# cblockyeesh.net
KiCad netlist of a schematic drawn in EAGLE
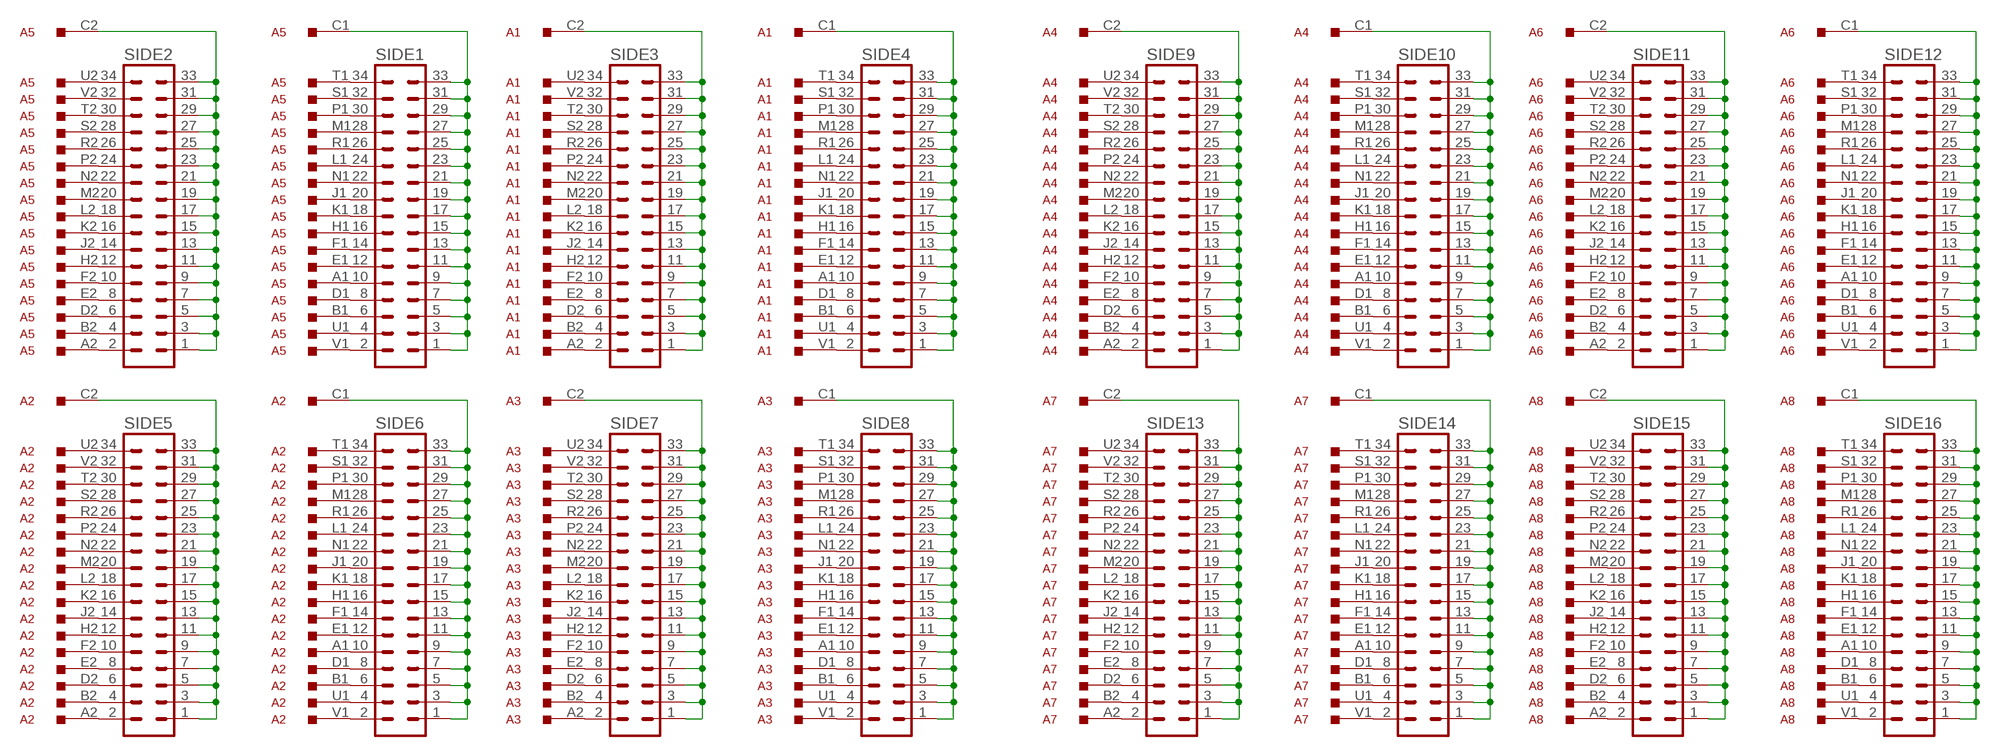
[diagram p0: schematic, sheet 1]

(export (version "E")
  (design (tool "Eeschema 10.0.6"))
  (components
    (comp (ref "A1")
      (value "M916")
      (footprint "eagle-import:H807")
      (libsource (lib "eagle-import") (part "M916"))
    )
    (comp (ref "A2")
      (value "M916")
      (footprint "eagle-import:H807")
      (libsource (lib "eagle-import") (part "M916"))
    )
    (comp (ref "A3")
      (value "M916")
      (footprint "eagle-import:H807")
      (libsource (lib "eagle-import") (part "M916"))
    )
    (comp (ref "A4")
      (value "M916")
      (footprint "eagle-import:H807")
      (libsource (lib "eagle-import") (part "M916"))
    )
    (comp (ref "A5")
      (value "M916")
      (footprint "eagle-import:H807")
      (libsource (lib "eagle-import") (part "M916"))
    )
    (comp (ref "A6")
      (value "M916")
      (footprint "eagle-import:H807")
      (libsource (lib "eagle-import") (part "M916"))
    )
    (comp (ref "A7")
      (value "M916")
      (footprint "eagle-import:H807")
      (libsource (lib "eagle-import") (part "M916"))
    )
    (comp (ref "A8")
      (value "M916")
      (footprint "eagle-import:H807")
      (libsource (lib "eagle-import") (part "M916"))
    )
    (comp (ref "SIDE1")
      (value "MA17-2")
      (footprint "eagle-import:MA17-2")
      (libsource (lib "eagle-import") (part "MA17-2"))
    )
    (comp (ref "SIDE2")
      (value "MA17-2")
      (footprint "eagle-import:MA17-2")
      (libsource (lib "eagle-import") (part "MA17-2"))
    )
    (comp (ref "SIDE3")
      (value "MA17-2")
      (footprint "eagle-import:MA17-2")
      (libsource (lib "eagle-import") (part "MA17-2"))
    )
    (comp (ref "SIDE4")
      (value "MA17-2")
      (footprint "eagle-import:MA17-2")
      (libsource (lib "eagle-import") (part "MA17-2"))
    )
    (comp (ref "SIDE5")
      (value "MA17-2")
      (footprint "eagle-import:MA17-2")
      (libsource (lib "eagle-import") (part "MA17-2"))
    )
    (comp (ref "SIDE6")
      (value "MA17-2")
      (footprint "eagle-import:MA17-2")
      (libsource (lib "eagle-import") (part "MA17-2"))
    )
    (comp (ref "SIDE7")
      (value "MA17-2")
      (footprint "eagle-import:MA17-2")
      (libsource (lib "eagle-import") (part "MA17-2"))
    )
    (comp (ref "SIDE8")
      (value "MA17-2")
      (footprint "eagle-import:MA17-2")
      (libsource (lib "eagle-import") (part "MA17-2"))
    )
    (comp (ref "SIDE9")
      (value "MA17-2")
      (footprint "eagle-import:MA17-2")
      (libsource (lib "eagle-import") (part "MA17-2"))
    )
    (comp (ref "SIDE10")
      (value "MA17-2")
      (footprint "eagle-import:MA17-2")
      (libsource (lib "eagle-import") (part "MA17-2"))
    )
    (comp (ref "SIDE11")
      (value "MA17-2")
      (footprint "eagle-import:MA17-2")
      (libsource (lib "eagle-import") (part "MA17-2"))
    )
    (comp (ref "SIDE12")
      (value "MA17-2")
      (footprint "eagle-import:MA17-2")
      (libsource (lib "eagle-import") (part "MA17-2"))
    )
    (comp (ref "SIDE13")
      (value "MA17-2")
      (footprint "eagle-import:MA17-2")
      (libsource (lib "eagle-import") (part "MA17-2"))
    )
    (comp (ref "SIDE14")
      (value "MA17-2")
      (footprint "eagle-import:MA17-2")
      (libsource (lib "eagle-import") (part "MA17-2"))
    )
    (comp (ref "SIDE15")
      (value "MA17-2")
      (footprint "eagle-import:MA17-2")
      (libsource (lib "eagle-import") (part "MA17-2"))
    )
    (comp (ref "SIDE16")
      (value "MA17-2")
      (footprint "eagle-import:MA17-2")
      (libsource (lib "eagle-import") (part "MA17-2"))
    )
  )
  (nets
    (net (code "1") (name "Net-(A1A-P$2)") (class "Default")
      (node (ref "A1") (pin "A1") (pinfunction "P$2_A1") (pintype "bidirectional"))
      (node (ref "SIDE4") (pin "10") (pinfunction "10_10") (pintype "passive"))
    )
    (net (code "2") (name "Net-(A1AA-P$2)") (class "Default")
      (node (ref "A1") (pin "R1") (pinfunction "P$2_R1") (pintype "bidirectional"))
      (node (ref "SIDE4") (pin "26") (pinfunction "26_26") (pintype "passive"))
    )
    (net (code "3") (name "Net-(A1AB-P$2)") (class "Default")
      (node (ref "A1") (pin "R2") (pinfunction "P$2_R2") (pintype "bidirectional"))
      (node (ref "SIDE3") (pin "26") (pinfunction "26_26") (pintype "passive"))
    )
    (net (code "4") (name "Net-(A1AC-P$2)") (class "Default")
      (node (ref "A1") (pin "S1") (pinfunction "P$2_S1") (pintype "bidirectional"))
      (node (ref "SIDE4") (pin "32") (pinfunction "32_32") (pintype "passive"))
    )
    (net (code "5") (name "Net-(A1AD-P$2)") (class "Default")
      (node (ref "A1") (pin "S2") (pinfunction "P$2_S2") (pintype "bidirectional"))
      (node (ref "SIDE3") (pin "28") (pinfunction "28_28") (pintype "passive"))
    )
    (net (code "6") (name "Net-(A1AE-P$2)") (class "Default")
      (node (ref "A1") (pin "T1") (pinfunction "P$2_T1") (pintype "bidirectional"))
      (node (ref "SIDE4") (pin "34") (pinfunction "34_34") (pintype "passive"))
    )
    (net (code "7") (name "Net-(A1AF-P$2)") (class "Default")
      (node (ref "A1") (pin "T2") (pinfunction "P$2_T2") (pintype "bidirectional"))
      (node (ref "SIDE3") (pin "30") (pinfunction "30_30") (pintype "passive"))
    )
    (net (code "8") (name "Net-(A1AG-P$2)") (class "Default")
      (node (ref "A1") (pin "U1") (pinfunction "P$2_U1") (pintype "bidirectional"))
      (node (ref "SIDE4") (pin "4") (pinfunction "4_4") (pintype "passive"))
    )
    (net (code "9") (name "Net-(A1AH-P$2)") (class "Default")
      (node (ref "A1") (pin "U2") (pinfunction "P$2_U2") (pintype "bidirectional"))
      (node (ref "SIDE3") (pin "34") (pinfunction "34_34") (pintype "passive"))
    )
    (net (code "10") (name "Net-(A1AI-P$2)") (class "Default")
      (node (ref "A1") (pin "V1") (pinfunction "P$2_V1") (pintype "bidirectional"))
      (node (ref "SIDE4") (pin "2") (pinfunction "2_2") (pintype "passive"))
    )
    (net (code "11") (name "Net-(A1AJ-P$2)") (class "Default")
      (node (ref "A1") (pin "V2") (pinfunction "P$2_V2") (pintype "bidirectional"))
      (node (ref "SIDE3") (pin "32") (pinfunction "32_32") (pintype "passive"))
    )
    (net (code "12") (name "Net-(A1B-P$2)") (class "Default")
      (node (ref "A1") (pin "A2") (pinfunction "P$2_A2") (pintype "bidirectional"))
      (node (ref "SIDE3") (pin "2") (pinfunction "2_2") (pintype "passive"))
    )
    (net (code "13") (name "Net-(A1C-P$2)") (class "Default")
      (node (ref "A1") (pin "B1") (pinfunction "P$2_B1") (pintype "bidirectional"))
      (node (ref "SIDE4") (pin "6") (pinfunction "6_6") (pintype "passive"))
    )
    (net (code "14") (name "Net-(A1D-P$2)") (class "Default")
      (node (ref "A1") (pin "B2") (pinfunction "P$2_B2") (pintype "bidirectional"))
      (node (ref "SIDE3") (pin "4") (pinfunction "4_4") (pintype "passive"))
    )
    (net (code "15") (name "Net-(A1E-P$2)") (class "Default")
      (node (ref "A1") (pin "C1") (pinfunction "P$2_C1") (pintype "bidirectional"))
      (node (ref "SIDE4") (pin "1") (pinfunction "1_1") (pintype "passive"))
      (node (ref "SIDE4") (pin "11") (pinfunction "11_11") (pintype "passive"))
      (node (ref "SIDE4") (pin "13") (pinfunction "13_13") (pintype "passive"))
      (node (ref "SIDE4") (pin "15") (pinfunction "15_15") (pintype "passive"))
      (node (ref "SIDE4") (pin "17") (pinfunction "17_17") (pintype "passive"))
      (node (ref "SIDE4") (pin "19") (pinfunction "19_19") (pintype "passive"))
      (node (ref "SIDE4") (pin "21") (pinfunction "21_21") (pintype "passive"))
      (node (ref "SIDE4") (pin "23") (pinfunction "23_23") (pintype "passive"))
      (node (ref "SIDE4") (pin "25") (pinfunction "25_25") (pintype "passive"))
      (node (ref "SIDE4") (pin "27") (pinfunction "27_27") (pintype "passive"))
      (node (ref "SIDE4") (pin "29") (pinfunction "29_29") (pintype "passive"))
      (node (ref "SIDE4") (pin "3") (pinfunction "3_3") (pintype "passive"))
      (node (ref "SIDE4") (pin "31") (pinfunction "31_31") (pintype "passive"))
      (node (ref "SIDE4") (pin "33") (pinfunction "33_33") (pintype "passive"))
      (node (ref "SIDE4") (pin "5") (pinfunction "5_5") (pintype "passive"))
      (node (ref "SIDE4") (pin "7") (pinfunction "7_7") (pintype "passive"))
      (node (ref "SIDE4") (pin "9") (pinfunction "9_9") (pintype "passive"))
    )
    (net (code "16") (name "Net-(A1F-P$2)") (class "Default")
      (node (ref "A1") (pin "C2") (pinfunction "P$2_C2") (pintype "bidirectional"))
      (node (ref "SIDE3") (pin "1") (pinfunction "1_1") (pintype "passive"))
      (node (ref "SIDE3") (pin "11") (pinfunction "11_11") (pintype "passive"))
      (node (ref "SIDE3") (pin "13") (pinfunction "13_13") (pintype "passive"))
      (node (ref "SIDE3") (pin "15") (pinfunction "15_15") (pintype "passive"))
      (node (ref "SIDE3") (pin "17") (pinfunction "17_17") (pintype "passive"))
      (node (ref "SIDE3") (pin "19") (pinfunction "19_19") (pintype "passive"))
      (node (ref "SIDE3") (pin "21") (pinfunction "21_21") (pintype "passive"))
      (node (ref "SIDE3") (pin "23") (pinfunction "23_23") (pintype "passive"))
      (node (ref "SIDE3") (pin "25") (pinfunction "25_25") (pintype "passive"))
      (node (ref "SIDE3") (pin "27") (pinfunction "27_27") (pintype "passive"))
      (node (ref "SIDE3") (pin "29") (pinfunction "29_29") (pintype "passive"))
      (node (ref "SIDE3") (pin "3") (pinfunction "3_3") (pintype "passive"))
      (node (ref "SIDE3") (pin "31") (pinfunction "31_31") (pintype "passive"))
      (node (ref "SIDE3") (pin "33") (pinfunction "33_33") (pintype "passive"))
      (node (ref "SIDE3") (pin "5") (pinfunction "5_5") (pintype "passive"))
      (node (ref "SIDE3") (pin "7") (pinfunction "7_7") (pintype "passive"))
      (node (ref "SIDE3") (pin "9") (pinfunction "9_9") (pintype "passive"))
    )
    (net (code "17") (name "Net-(A1G-P$2)") (class "Default")
      (node (ref "A1") (pin "D1") (pinfunction "P$2_D1") (pintype "bidirectional"))
      (node (ref "SIDE4") (pin "8") (pinfunction "8_8") (pintype "passive"))
    )
    (net (code "18") (name "Net-(A1H-P$2)") (class "Default")
      (node (ref "A1") (pin "D2") (pinfunction "P$2_D2") (pintype "bidirectional"))
      (node (ref "SIDE3") (pin "6") (pinfunction "6_6") (pintype "passive"))
    )
    (net (code "19") (name "Net-(A1I-P$2)") (class "Default")
      (node (ref "A1") (pin "E1") (pinfunction "P$2_E1") (pintype "bidirectional"))
      (node (ref "SIDE4") (pin "12") (pinfunction "12_12") (pintype "passive"))
    )
    (net (code "20") (name "Net-(A1J-P$2)") (class "Default")
      (node (ref "A1") (pin "E2") (pinfunction "P$2_E2") (pintype "bidirectional"))
      (node (ref "SIDE3") (pin "8") (pinfunction "8_8") (pintype "passive"))
    )
    (net (code "21") (name "Net-(A1K-P$2)") (class "Default")
      (node (ref "A1") (pin "F1") (pinfunction "P$2_F1") (pintype "bidirectional"))
      (node (ref "SIDE4") (pin "14") (pinfunction "14_14") (pintype "passive"))
    )
    (net (code "22") (name "Net-(A1L-P$2)") (class "Default")
      (node (ref "A1") (pin "F2") (pinfunction "P$2_F2") (pintype "bidirectional"))
      (node (ref "SIDE3") (pin "10") (pinfunction "10_10") (pintype "passive"))
    )
    (net (code "23") (name "Net-(A1M-P$2)") (class "Default")
      (node (ref "A1") (pin "H1") (pinfunction "P$2_H1") (pintype "bidirectional"))
      (node (ref "SIDE4") (pin "16") (pinfunction "16_16") (pintype "passive"))
    )
    (net (code "24") (name "Net-(A1N-P$2)") (class "Default")
      (node (ref "A1") (pin "H2") (pinfunction "P$2_H2") (pintype "bidirectional"))
      (node (ref "SIDE3") (pin "12") (pinfunction "12_12") (pintype "passive"))
    )
    (net (code "25") (name "Net-(A1O-P$2)") (class "Default")
      (node (ref "A1") (pin "J1") (pinfunction "P$2_J1") (pintype "bidirectional"))
      (node (ref "SIDE4") (pin "20") (pinfunction "20_20") (pintype "passive"))
    )
    (net (code "26") (name "Net-(A1P-P$2)") (class "Default")
      (node (ref "A1") (pin "J2") (pinfunction "P$2_J2") (pintype "bidirectional"))
      (node (ref "SIDE3") (pin "14") (pinfunction "14_14") (pintype "passive"))
    )
    (net (code "27") (name "Net-(A1Q-P$2)") (class "Default")
      (node (ref "A1") (pin "K1") (pinfunction "P$2_K1") (pintype "bidirectional"))
      (node (ref "SIDE4") (pin "18") (pinfunction "18_18") (pintype "passive"))
    )
    (net (code "28") (name "Net-(A1R-P$2)") (class "Default")
      (node (ref "A1") (pin "K2") (pinfunction "P$2_K2") (pintype "bidirectional"))
      (node (ref "SIDE3") (pin "16") (pinfunction "16_16") (pintype "passive"))
    )
    (net (code "29") (name "Net-(A1S-P$2)") (class "Default")
      (node (ref "A1") (pin "L1") (pinfunction "P$2_L1") (pintype "bidirectional"))
      (node (ref "SIDE4") (pin "24") (pinfunction "24_24") (pintype "passive"))
    )
    (net (code "30") (name "Net-(A1T-P$2)") (class "Default")
      (node (ref "A1") (pin "L2") (pinfunction "P$2_L2") (pintype "bidirectional"))
      (node (ref "SIDE3") (pin "18") (pinfunction "18_18") (pintype "passive"))
    )
    (net (code "31") (name "Net-(A1U-P$2)") (class "Default")
      (node (ref "A1") (pin "M1") (pinfunction "P$2_M1") (pintype "bidirectional"))
      (node (ref "SIDE4") (pin "28") (pinfunction "28_28") (pintype "passive"))
    )
    (net (code "32") (name "Net-(A1V-P$2)") (class "Default")
      (node (ref "A1") (pin "M2") (pinfunction "P$2_M2") (pintype "bidirectional"))
      (node (ref "SIDE3") (pin "20") (pinfunction "20_20") (pintype "passive"))
    )
    (net (code "33") (name "Net-(A1W-P$2)") (class "Default")
      (node (ref "A1") (pin "N1") (pinfunction "P$2_N1") (pintype "bidirectional"))
      (node (ref "SIDE4") (pin "22") (pinfunction "22_22") (pintype "passive"))
    )
    (net (code "34") (name "Net-(A1X-P$2)") (class "Default")
      (node (ref "A1") (pin "N2") (pinfunction "P$2_N2") (pintype "bidirectional"))
      (node (ref "SIDE3") (pin "22") (pinfunction "22_22") (pintype "passive"))
    )
    (net (code "35") (name "Net-(A1Y-P$2)") (class "Default")
      (node (ref "A1") (pin "P1") (pinfunction "P$2_P1") (pintype "bidirectional"))
      (node (ref "SIDE4") (pin "30") (pinfunction "30_30") (pintype "passive"))
    )
    (net (code "36") (name "Net-(A1Z-P$2)") (class "Default")
      (node (ref "A1") (pin "P2") (pinfunction "P$2_P2") (pintype "bidirectional"))
      (node (ref "SIDE3") (pin "24") (pinfunction "24_24") (pintype "passive"))
    )
    (net (code "37") (name "Net-(A2A-P$2)") (class "Default")
      (node (ref "A2") (pin "A1") (pinfunction "P$2_A1") (pintype "bidirectional"))
      (node (ref "SIDE6") (pin "10") (pinfunction "10_10") (pintype "passive"))
    )
    (net (code "38") (name "Net-(A2AA-P$2)") (class "Default")
      (node (ref "A2") (pin "R1") (pinfunction "P$2_R1") (pintype "bidirectional"))
      (node (ref "SIDE6") (pin "26") (pinfunction "26_26") (pintype "passive"))
    )
    (net (code "39") (name "Net-(A2AB-P$2)") (class "Default")
      (node (ref "A2") (pin "R2") (pinfunction "P$2_R2") (pintype "bidirectional"))
      (node (ref "SIDE5") (pin "26") (pinfunction "26_26") (pintype "passive"))
    )
    (net (code "40") (name "Net-(A2AC-P$2)") (class "Default")
      (node (ref "A2") (pin "S1") (pinfunction "P$2_S1") (pintype "bidirectional"))
      (node (ref "SIDE6") (pin "32") (pinfunction "32_32") (pintype "passive"))
    )
    (net (code "41") (name "Net-(A2AD-P$2)") (class "Default")
      (node (ref "A2") (pin "S2") (pinfunction "P$2_S2") (pintype "bidirectional"))
      (node (ref "SIDE5") (pin "28") (pinfunction "28_28") (pintype "passive"))
    )
    (net (code "42") (name "Net-(A2AE-P$2)") (class "Default")
      (node (ref "A2") (pin "T1") (pinfunction "P$2_T1") (pintype "bidirectional"))
      (node (ref "SIDE6") (pin "34") (pinfunction "34_34") (pintype "passive"))
    )
    (net (code "43") (name "Net-(A2AF-P$2)") (class "Default")
      (node (ref "A2") (pin "T2") (pinfunction "P$2_T2") (pintype "bidirectional"))
      (node (ref "SIDE5") (pin "30") (pinfunction "30_30") (pintype "passive"))
    )
    (net (code "44") (name "Net-(A2AG-P$2)") (class "Default")
      (node (ref "A2") (pin "U1") (pinfunction "P$2_U1") (pintype "bidirectional"))
      (node (ref "SIDE6") (pin "4") (pinfunction "4_4") (pintype "passive"))
    )
    (net (code "45") (name "Net-(A2AH-P$2)") (class "Default")
      (node (ref "A2") (pin "U2") (pinfunction "P$2_U2") (pintype "bidirectional"))
      (node (ref "SIDE5") (pin "34") (pinfunction "34_34") (pintype "passive"))
    )
    (net (code "46") (name "Net-(A2AI-P$2)") (class "Default")
      (node (ref "A2") (pin "V1") (pinfunction "P$2_V1") (pintype "bidirectional"))
      (node (ref "SIDE6") (pin "2") (pinfunction "2_2") (pintype "passive"))
    )
    (net (code "47") (name "Net-(A2AJ-P$2)") (class "Default")
      (node (ref "A2") (pin "V2") (pinfunction "P$2_V2") (pintype "bidirectional"))
      (node (ref "SIDE5") (pin "32") (pinfunction "32_32") (pintype "passive"))
    )
    (net (code "48") (name "Net-(A2B-P$2)") (class "Default")
      (node (ref "A2") (pin "A2") (pinfunction "P$2_A2") (pintype "bidirectional"))
      (node (ref "SIDE5") (pin "2") (pinfunction "2_2") (pintype "passive"))
    )
    (net (code "49") (name "Net-(A2C-P$2)") (class "Default")
      (node (ref "A2") (pin "B1") (pinfunction "P$2_B1") (pintype "bidirectional"))
      (node (ref "SIDE6") (pin "6") (pinfunction "6_6") (pintype "passive"))
    )
    (net (code "50") (name "Net-(A2D-P$2)") (class "Default")
      (node (ref "A2") (pin "B2") (pinfunction "P$2_B2") (pintype "bidirectional"))
      (node (ref "SIDE5") (pin "4") (pinfunction "4_4") (pintype "passive"))
    )
    (net (code "51") (name "Net-(A2E-P$2)") (class "Default")
      (node (ref "A2") (pin "C1") (pinfunction "P$2_C1") (pintype "bidirectional"))
      (node (ref "SIDE6") (pin "1") (pinfunction "1_1") (pintype "passive"))
      (node (ref "SIDE6") (pin "11") (pinfunction "11_11") (pintype "passive"))
      (node (ref "SIDE6") (pin "13") (pinfunction "13_13") (pintype "passive"))
      (node (ref "SIDE6") (pin "15") (pinfunction "15_15") (pintype "passive"))
      (node (ref "SIDE6") (pin "17") (pinfunction "17_17") (pintype "passive"))
      (node (ref "SIDE6") (pin "19") (pinfunction "19_19") (pintype "passive"))
      (node (ref "SIDE6") (pin "21") (pinfunction "21_21") (pintype "passive"))
      (node (ref "SIDE6") (pin "23") (pinfunction "23_23") (pintype "passive"))
      (node (ref "SIDE6") (pin "25") (pinfunction "25_25") (pintype "passive"))
      (node (ref "SIDE6") (pin "27") (pinfunction "27_27") (pintype "passive"))
      (node (ref "SIDE6") (pin "29") (pinfunction "29_29") (pintype "passive"))
      (node (ref "SIDE6") (pin "3") (pinfunction "3_3") (pintype "passive"))
      (node (ref "SIDE6") (pin "31") (pinfunction "31_31") (pintype "passive"))
      (node (ref "SIDE6") (pin "33") (pinfunction "33_33") (pintype "passive"))
      (node (ref "SIDE6") (pin "5") (pinfunction "5_5") (pintype "passive"))
      (node (ref "SIDE6") (pin "7") (pinfunction "7_7") (pintype "passive"))
      (node (ref "SIDE6") (pin "9") (pinfunction "9_9") (pintype "passive"))
    )
    (net (code "52") (name "Net-(A2F-P$2)") (class "Default")
      (node (ref "A2") (pin "C2") (pinfunction "P$2_C2") (pintype "bidirectional"))
      (node (ref "SIDE5") (pin "1") (pinfunction "1_1") (pintype "passive"))
      (node (ref "SIDE5") (pin "11") (pinfunction "11_11") (pintype "passive"))
      (node (ref "SIDE5") (pin "13") (pinfunction "13_13") (pintype "passive"))
      (node (ref "SIDE5") (pin "15") (pinfunction "15_15") (pintype "passive"))
      (node (ref "SIDE5") (pin "17") (pinfunction "17_17") (pintype "passive"))
      (node (ref "SIDE5") (pin "19") (pinfunction "19_19") (pintype "passive"))
      (node (ref "SIDE5") (pin "21") (pinfunction "21_21") (pintype "passive"))
      (node (ref "SIDE5") (pin "23") (pinfunction "23_23") (pintype "passive"))
      (node (ref "SIDE5") (pin "25") (pinfunction "25_25") (pintype "passive"))
      (node (ref "SIDE5") (pin "27") (pinfunction "27_27") (pintype "passive"))
      (node (ref "SIDE5") (pin "29") (pinfunction "29_29") (pintype "passive"))
      (node (ref "SIDE5") (pin "3") (pinfunction "3_3") (pintype "passive"))
      (node (ref "SIDE5") (pin "31") (pinfunction "31_31") (pintype "passive"))
      (node (ref "SIDE5") (pin "33") (pinfunction "33_33") (pintype "passive"))
      (node (ref "SIDE5") (pin "5") (pinfunction "5_5") (pintype "passive"))
      (node (ref "SIDE5") (pin "7") (pinfunction "7_7") (pintype "passive"))
      (node (ref "SIDE5") (pin "9") (pinfunction "9_9") (pintype "passive"))
    )
    (net (code "53") (name "Net-(A2G-P$2)") (class "Default")
      (node (ref "A2") (pin "D1") (pinfunction "P$2_D1") (pintype "bidirectional"))
      (node (ref "SIDE6") (pin "8") (pinfunction "8_8") (pintype "passive"))
    )
    (net (code "54") (name "Net-(A2H-P$2)") (class "Default")
      (node (ref "A2") (pin "D2") (pinfunction "P$2_D2") (pintype "bidirectional"))
      (node (ref "SIDE5") (pin "6") (pinfunction "6_6") (pintype "passive"))
    )
    (net (code "55") (name "Net-(A2I-P$2)") (class "Default")
      (node (ref "A2") (pin "E1") (pinfunction "P$2_E1") (pintype "bidirectional"))
      (node (ref "SIDE6") (pin "12") (pinfunction "12_12") (pintype "passive"))
    )
    (net (code "56") (name "Net-(A2J-P$2)") (class "Default")
      (node (ref "A2") (pin "E2") (pinfunction "P$2_E2") (pintype "bidirectional"))
      (node (ref "SIDE5") (pin "8") (pinfunction "8_8") (pintype "passive"))
    )
    (net (code "57") (name "Net-(A2K-P$2)") (class "Default")
      (node (ref "A2") (pin "F1") (pinfunction "P$2_F1") (pintype "bidirectional"))
      (node (ref "SIDE6") (pin "14") (pinfunction "14_14") (pintype "passive"))
    )
    (net (code "58") (name "Net-(A2L-P$2)") (class "Default")
      (node (ref "A2") (pin "F2") (pinfunction "P$2_F2") (pintype "bidirectional"))
      (node (ref "SIDE5") (pin "10") (pinfunction "10_10") (pintype "passive"))
    )
    (net (code "59") (name "Net-(A2M-P$2)") (class "Default")
      (node (ref "A2") (pin "H1") (pinfunction "P$2_H1") (pintype "bidirectional"))
      (node (ref "SIDE6") (pin "16") (pinfunction "16_16") (pintype "passive"))
    )
    (net (code "60") (name "Net-(A2N-P$2)") (class "Default")
      (node (ref "A2") (pin "H2") (pinfunction "P$2_H2") (pintype "bidirectional"))
      (node (ref "SIDE5") (pin "12") (pinfunction "12_12") (pintype "passive"))
    )
    (net (code "61") (name "Net-(A2O-P$2)") (class "Default")
      (node (ref "A2") (pin "J1") (pinfunction "P$2_J1") (pintype "bidirectional"))
      (node (ref "SIDE6") (pin "20") (pinfunction "20_20") (pintype "passive"))
    )
    (net (code "62") (name "Net-(A2P-P$2)") (class "Default")
      (node (ref "A2") (pin "J2") (pinfunction "P$2_J2") (pintype "bidirectional"))
      (node (ref "SIDE5") (pin "14") (pinfunction "14_14") (pintype "passive"))
    )
    (net (code "63") (name "Net-(A2Q-P$2)") (class "Default")
      (node (ref "A2") (pin "K1") (pinfunction "P$2_K1") (pintype "bidirectional"))
      (node (ref "SIDE6") (pin "18") (pinfunction "18_18") (pintype "passive"))
    )
    (net (code "64") (name "Net-(A2R-P$2)") (class "Default")
      (node (ref "A2") (pin "K2") (pinfunction "P$2_K2") (pintype "bidirectional"))
      (node (ref "SIDE5") (pin "16") (pinfunction "16_16") (pintype "passive"))
    )
    (net (code "65") (name "Net-(A2S-P$2)") (class "Default")
      (node (ref "A2") (pin "L1") (pinfunction "P$2_L1") (pintype "bidirectional"))
      (node (ref "SIDE6") (pin "24") (pinfunction "24_24") (pintype "passive"))
    )
    (net (code "66") (name "Net-(A2T-P$2)") (class "Default")
      (node (ref "A2") (pin "L2") (pinfunction "P$2_L2") (pintype "bidirectional"))
      (node (ref "SIDE5") (pin "18") (pinfunction "18_18") (pintype "passive"))
    )
    (net (code "67") (name "Net-(A2U-P$2)") (class "Default")
      (node (ref "A2") (pin "M1") (pinfunction "P$2_M1") (pintype "bidirectional"))
      (node (ref "SIDE6") (pin "28") (pinfunction "28_28") (pintype "passive"))
    )
    (net (code "68") (name "Net-(A2V-P$2)") (class "Default")
      (node (ref "A2") (pin "M2") (pinfunction "P$2_M2") (pintype "bidirectional"))
      (node (ref "SIDE5") (pin "20") (pinfunction "20_20") (pintype "passive"))
    )
    (net (code "69") (name "Net-(A2W-P$2)") (class "Default")
      (node (ref "A2") (pin "N1") (pinfunction "P$2_N1") (pintype "bidirectional"))
      (node (ref "SIDE6") (pin "22") (pinfunction "22_22") (pintype "passive"))
    )
    (net (code "70") (name "Net-(A2X-P$2)") (class "Default")
      (node (ref "A2") (pin "N2") (pinfunction "P$2_N2") (pintype "bidirectional"))
      (node (ref "SIDE5") (pin "22") (pinfunction "22_22") (pintype "passive"))
    )
    (net (code "71") (name "Net-(A2Y-P$2)") (class "Default")
      (node (ref "A2") (pin "P1") (pinfunction "P$2_P1") (pintype "bidirectional"))
      (node (ref "SIDE6") (pin "30") (pinfunction "30_30") (pintype "passive"))
    )
    (net (code "72") (name "Net-(A2Z-P$2)") (class "Default")
      (node (ref "A2") (pin "P2") (pinfunction "P$2_P2") (pintype "bidirectional"))
      (node (ref "SIDE5") (pin "24") (pinfunction "24_24") (pintype "passive"))
    )
    (net (code "73") (name "Net-(A3A-P$2)") (class "Default")
      (node (ref "A3") (pin "A1") (pinfunction "P$2_A1") (pintype "bidirectional"))
      (node (ref "SIDE8") (pin "10") (pinfunction "10_10") (pintype "passive"))
    )
    (net (code "74") (name "Net-(A3AA-P$2)") (class "Default")
      (node (ref "A3") (pin "R1") (pinfunction "P$2_R1") (pintype "bidirectional"))
      (node (ref "SIDE8") (pin "26") (pinfunction "26_26") (pintype "passive"))
    )
    (net (code "75") (name "Net-(A3AB-P$2)") (class "Default")
      (node (ref "A3") (pin "R2") (pinfunction "P$2_R2") (pintype "bidirectional"))
      (node (ref "SIDE7") (pin "26") (pinfunction "26_26") (pintype "passive"))
    )
    (net (code "76") (name "Net-(A3AC-P$2)") (class "Default")
      (node (ref "A3") (pin "S1") (pinfunction "P$2_S1") (pintype "bidirectional"))
      (node (ref "SIDE8") (pin "32") (pinfunction "32_32") (pintype "passive"))
    )
    (net (code "77") (name "Net-(A3AD-P$2)") (class "Default")
      (node (ref "A3") (pin "S2") (pinfunction "P$2_S2") (pintype "bidirectional"))
      (node (ref "SIDE7") (pin "28") (pinfunction "28_28") (pintype "passive"))
    )
    (net (code "78") (name "Net-(A3AE-P$2)") (class "Default")
      (node (ref "A3") (pin "T1") (pinfunction "P$2_T1") (pintype "bidirectional"))
      (node (ref "SIDE8") (pin "34") (pinfunction "34_34") (pintype "passive"))
    )
    (net (code "79") (name "Net-(A3AF-P$2)") (class "Default")
      (node (ref "A3") (pin "T2") (pinfunction "P$2_T2") (pintype "bidirectional"))
      (node (ref "SIDE7") (pin "30") (pinfunction "30_30") (pintype "passive"))
    )
    (net (code "80") (name "Net-(A3AG-P$2)") (class "Default")
      (node (ref "A3") (pin "U1") (pinfunction "P$2_U1") (pintype "bidirectional"))
      (node (ref "SIDE8") (pin "4") (pinfunction "4_4") (pintype "passive"))
    )
    (net (code "81") (name "Net-(A3AH-P$2)") (class "Default")
      (node (ref "A3") (pin "U2") (pinfunction "P$2_U2") (pintype "bidirectional"))
      (node (ref "SIDE7") (pin "34") (pinfunction "34_34") (pintype "passive"))
    )
    (net (code "82") (name "Net-(A3AI-P$2)") (class "Default")
      (node (ref "A3") (pin "V1") (pinfunction "P$2_V1") (pintype "bidirectional"))
      (node (ref "SIDE8") (pin "2") (pinfunction "2_2") (pintype "passive"))
    )
    (net (code "83") (name "Net-(A3AJ-P$2)") (class "Default")
      (node (ref "A3") (pin "V2") (pinfunction "P$2_V2") (pintype "bidirectional"))
      (node (ref "SIDE7") (pin "32") (pinfunction "32_32") (pintype "passive"))
    )
    (net (code "84") (name "Net-(A3B-P$2)") (class "Default")
      (node (ref "A3") (pin "A2") (pinfunction "P$2_A2") (pintype "bidirectional"))
      (node (ref "SIDE7") (pin "2") (pinfunction "2_2") (pintype "passive"))
    )
    (net (code "85") (name "Net-(A3C-P$2)") (class "Default")
      (node (ref "A3") (pin "B1") (pinfunction "P$2_B1") (pintype "bidirectional"))
      (node (ref "SIDE8") (pin "6") (pinfunction "6_6") (pintype "passive"))
    )
    (net (code "86") (name "Net-(A3D-P$2)") (class "Default")
      (node (ref "A3") (pin "B2") (pinfunction "P$2_B2") (pintype "bidirectional"))
      (node (ref "SIDE7") (pin "4") (pinfunction "4_4") (pintype "passive"))
    )
    (net (code "87") (name "Net-(A3E-P$2)") (class "Default")
      (node (ref "A3") (pin "C1") (pinfunction "P$2_C1") (pintype "bidirectional"))
      (node (ref "SIDE8") (pin "1") (pinfunction "1_1") (pintype "passive"))
      (node (ref "SIDE8") (pin "11") (pinfunction "11_11") (pintype "passive"))
      (node (ref "SIDE8") (pin "13") (pinfunction "13_13") (pintype "passive"))
      (node (ref "SIDE8") (pin "15") (pinfunction "15_15") (pintype "passive"))
      (node (ref "SIDE8") (pin "17") (pinfunction "17_17") (pintype "passive"))
      (node (ref "SIDE8") (pin "19") (pinfunction "19_19") (pintype "passive"))
      (node (ref "SIDE8") (pin "21") (pinfunction "21_21") (pintype "passive"))
      (node (ref "SIDE8") (pin "23") (pinfunction "23_23") (pintype "passive"))
      (node (ref "SIDE8") (pin "25") (pinfunction "25_25") (pintype "passive"))
      (node (ref "SIDE8") (pin "27") (pinfunction "27_27") (pintype "passive"))
      (node (ref "SIDE8") (pin "29") (pinfunction "29_29") (pintype "passive"))
      (node (ref "SIDE8") (pin "3") (pinfunction "3_3") (pintype "passive"))
      (node (ref "SIDE8") (pin "31") (pinfunction "31_31") (pintype "passive"))
      (node (ref "SIDE8") (pin "33") (pinfunction "33_33") (pintype "passive"))
      (node (ref "SIDE8") (pin "5") (pinfunction "5_5") (pintype "passive"))
      (node (ref "SIDE8") (pin "7") (pinfunction "7_7") (pintype "passive"))
      (node (ref "SIDE8") (pin "9") (pinfunction "9_9") (pintype "passive"))
    )
    (net (code "88") (name "Net-(A3F-P$2)") (class "Default")
      (node (ref "A3") (pin "C2") (pinfunction "P$2_C2") (pintype "bidirectional"))
      (node (ref "SIDE7") (pin "1") (pinfunction "1_1") (pintype "passive"))
      (node (ref "SIDE7") (pin "11") (pinfunction "11_11") (pintype "passive"))
      (node (ref "SIDE7") (pin "13") (pinfunction "13_13") (pintype "passive"))
      (node (ref "SIDE7") (pin "15") (pinfunction "15_15") (pintype "passive"))
      (node (ref "SIDE7") (pin "17") (pinfunction "17_17") (pintype "passive"))
      (node (ref "SIDE7") (pin "19") (pinfunction "19_19") (pintype "passive"))
      (node (ref "SIDE7") (pin "21") (pinfunction "21_21") (pintype "passive"))
      (node (ref "SIDE7") (pin "23") (pinfunction "23_23") (pintype "passive"))
      (node (ref "SIDE7") (pin "25") (pinfunction "25_25") (pintype "passive"))
      (node (ref "SIDE7") (pin "27") (pinfunction "27_27") (pintype "passive"))
      (node (ref "SIDE7") (pin "29") (pinfunction "29_29") (pintype "passive"))
      (node (ref "SIDE7") (pin "3") (pinfunction "3_3") (pintype "passive"))
      (node (ref "SIDE7") (pin "31") (pinfunction "31_31") (pintype "passive"))
      (node (ref "SIDE7") (pin "33") (pinfunction "33_33") (pintype "passive"))
      (node (ref "SIDE7") (pin "5") (pinfunction "5_5") (pintype "passive"))
      (node (ref "SIDE7") (pin "7") (pinfunction "7_7") (pintype "passive"))
      (node (ref "SIDE7") (pin "9") (pinfunction "9_9") (pintype "passive"))
    )
    (net (code "89") (name "Net-(A3G-P$2)") (class "Default")
      (node (ref "A3") (pin "D1") (pinfunction "P$2_D1") (pintype "bidirectional"))
      (node (ref "SIDE8") (pin "8") (pinfunction "8_8") (pintype "passive"))
    )
    (net (code "90") (name "Net-(A3H-P$2)") (class "Default")
      (node (ref "A3") (pin "D2") (pinfunction "P$2_D2") (pintype "bidirectional"))
      (node (ref "SIDE7") (pin "6") (pinfunction "6_6") (pintype "passive"))
    )
    (net (code "91") (name "Net-(A3I-P$2)") (class "Default")
      (node (ref "A3") (pin "E1") (pinfunction "P$2_E1") (pintype "bidirectional"))
      (node (ref "SIDE8") (pin "12") (pinfunction "12_12") (pintype "passive"))
    )
    (net (code "92") (name "Net-(A3J-P$2)") (class "Default")
      (node (ref "A3") (pin "E2") (pinfunction "P$2_E2") (pintype "bidirectional"))
      (node (ref "SIDE7") (pin "8") (pinfunction "8_8") (pintype "passive"))
    )
    (net (code "93") (name "Net-(A3K-P$2)") (class "Default")
      (node (ref "A3") (pin "F1") (pinfunction "P$2_F1") (pintype "bidirectional"))
      (node (ref "SIDE8") (pin "14") (pinfunction "14_14") (pintype "passive"))
    )
    (net (code "94") (name "Net-(A3L-P$2)") (class "Default")
      (node (ref "A3") (pin "F2") (pinfunction "P$2_F2") (pintype "bidirectional"))
      (node (ref "SIDE7") (pin "10") (pinfunction "10_10") (pintype "passive"))
    )
    (net (code "95") (name "Net-(A3M-P$2)") (class "Default")
      (node (ref "A3") (pin "H1") (pinfunction "P$2_H1") (pintype "bidirectional"))
      (node (ref "SIDE8") (pin "16") (pinfunction "16_16") (pintype "passive"))
    )
    (net (code "96") (name "Net-(A3N-P$2)") (class "Default")
      (node (ref "A3") (pin "H2") (pinfunction "P$2_H2") (pintype "bidirectional"))
      (node (ref "SIDE7") (pin "12") (pinfunction "12_12") (pintype "passive"))
    )
    (net (code "97") (name "Net-(A3O-P$2)") (class "Default")
      (node (ref "A3") (pin "J1") (pinfunction "P$2_J1") (pintype "bidirectional"))
      (node (ref "SIDE8") (pin "20") (pinfunction "20_20") (pintype "passive"))
    )
    (net (code "98") (name "Net-(A3P-P$2)") (class "Default")
      (node (ref "A3") (pin "J2") (pinfunction "P$2_J2") (pintype "bidirectional"))
      (node (ref "SIDE7") (pin "14") (pinfunction "14_14") (pintype "passive"))
    )
    (net (code "99") (name "Net-(A3Q-P$2)") (class "Default")
      (node (ref "A3") (pin "K1") (pinfunction "P$2_K1") (pintype "bidirectional"))
      (node (ref "SIDE8") (pin "18") (pinfunction "18_18") (pintype "passive"))
    )
    (net (code "100") (name "Net-(A3R-P$2)") (class "Default")
      (node (ref "A3") (pin "K2") (pinfunction "P$2_K2") (pintype "bidirectional"))
      (node (ref "SIDE7") (pin "16") (pinfunction "16_16") (pintype "passive"))
    )
    (net (code "101") (name "Net-(A3S-P$2)") (class "Default")
      (node (ref "A3") (pin "L1") (pinfunction "P$2_L1") (pintype "bidirectional"))
      (node (ref "SIDE8") (pin "24") (pinfunction "24_24") (pintype "passive"))
    )
    (net (code "102") (name "Net-(A3T-P$2)") (class "Default")
      (node (ref "A3") (pin "L2") (pinfunction "P$2_L2") (pintype "bidirectional"))
      (node (ref "SIDE7") (pin "18") (pinfunction "18_18") (pintype "passive"))
    )
    (net (code "103") (name "Net-(A3U-P$2)") (class "Default")
      (node (ref "A3") (pin "M1") (pinfunction "P$2_M1") (pintype "bidirectional"))
      (node (ref "SIDE8") (pin "28") (pinfunction "28_28") (pintype "passive"))
    )
    (net (code "104") (name "Net-(A3V-P$2)") (class "Default")
      (node (ref "A3") (pin "M2") (pinfunction "P$2_M2") (pintype "bidirectional"))
      (node (ref "SIDE7") (pin "20") (pinfunction "20_20") (pintype "passive"))
    )
    (net (code "105") (name "Net-(A3W-P$2)") (class "Default")
      (node (ref "A3") (pin "N1") (pinfunction "P$2_N1") (pintype "bidirectional"))
      (node (ref "SIDE8") (pin "22") (pinfunction "22_22") (pintype "passive"))
    )
    (net (code "106") (name "Net-(A3X-P$2)") (class "Default")
      (node (ref "A3") (pin "N2") (pinfunction "P$2_N2") (pintype "bidirectional"))
      (node (ref "SIDE7") (pin "22") (pinfunction "22_22") (pintype "passive"))
    )
    (net (code "107") (name "Net-(A3Y-P$2)") (class "Default")
      (node (ref "A3") (pin "P1") (pinfunction "P$2_P1") (pintype "bidirectional"))
      (node (ref "SIDE8") (pin "30") (pinfunction "30_30") (pintype "passive"))
    )
    (net (code "108") (name "Net-(A3Z-P$2)") (class "Default")
      (node (ref "A3") (pin "P2") (pinfunction "P$2_P2") (pintype "bidirectional"))
      (node (ref "SIDE7") (pin "24") (pinfunction "24_24") (pintype "passive"))
    )
    (net (code "109") (name "Net-(A4A-P$2)") (class "Default")
      (node (ref "A4") (pin "A1") (pinfunction "P$2_A1") (pintype "bidirectional"))
      (node (ref "SIDE10") (pin "10") (pinfunction "10_10") (pintype "passive"))
    )
    (net (code "110") (name "Net-(A4AA-P$2)") (class "Default")
      (node (ref "A4") (pin "R1") (pinfunction "P$2_R1") (pintype "bidirectional"))
      (node (ref "SIDE10") (pin "26") (pinfunction "26_26") (pintype "passive"))
    )
    (net (code "111") (name "Net-(A4AB-P$2)") (class "Default")
      (node (ref "A4") (pin "R2") (pinfunction "P$2_R2") (pintype "bidirectional"))
      (node (ref "SIDE9") (pin "26") (pinfunction "26_26") (pintype "passive"))
    )
    (net (code "112") (name "Net-(A4AC-P$2)") (class "Default")
      (node (ref "A4") (pin "S1") (pinfunction "P$2_S1") (pintype "bidirectional"))
      (node (ref "SIDE10") (pin "32") (pinfunction "32_32") (pintype "passive"))
    )
    (net (code "113") (name "Net-(A4AD-P$2)") (class "Default")
      (node (ref "A4") (pin "S2") (pinfunction "P$2_S2") (pintype "bidirectional"))
      (node (ref "SIDE9") (pin "28") (pinfunction "28_28") (pintype "passive"))
    )
    (net (code "114") (name "Net-(A4AE-P$2)") (class "Default")
      (node (ref "A4") (pin "T1") (pinfunction "P$2_T1") (pintype "bidirectional"))
      (node (ref "SIDE10") (pin "34") (pinfunction "34_34") (pintype "passive"))
    )
    (net (code "115") (name "Net-(A4AF-P$2)") (class "Default")
      (node (ref "A4") (pin "T2") (pinfunction "P$2_T2") (pintype "bidirectional"))
      (node (ref "SIDE9") (pin "30") (pinfunction "30_30") (pintype "passive"))
    )
    (net (code "116") (name "Net-(A4AG-P$2)") (class "Default")
      (node (ref "A4") (pin "U1") (pinfunction "P$2_U1") (pintype "bidirectional"))
      (node (ref "SIDE10") (pin "4") (pinfunction "4_4") (pintype "passive"))
    )
    (net (code "117") (name "Net-(A4AH-P$2)") (class "Default")
      (node (ref "A4") (pin "U2") (pinfunction "P$2_U2") (pintype "bidirectional"))
      (node (ref "SIDE9") (pin "34") (pinfunction "34_34") (pintype "passive"))
    )
    (net (code "118") (name "Net-(A4AI-P$2)") (class "Default")
      (node (ref "A4") (pin "V1") (pinfunction "P$2_V1") (pintype "bidirectional"))
      (node (ref "SIDE10") (pin "2") (pinfunction "2_2") (pintype "passive"))
    )
    (net (code "119") (name "Net-(A4AJ-P$2)") (class "Default")
      (node (ref "A4") (pin "V2") (pinfunction "P$2_V2") (pintype "bidirectional"))
      (node (ref "SIDE9") (pin "32") (pinfunction "32_32") (pintype "passive"))
    )
    (net (code "120") (name "Net-(A4B-P$2)") (class "Default")
      (node (ref "A4") (pin "A2") (pinfunction "P$2_A2") (pintype "bidirectional"))
      (node (ref "SIDE9") (pin "2") (pinfunction "2_2") (pintype "passive"))
    )
    (net (code "121") (name "Net-(A4C-P$2)") (class "Default")
      (node (ref "A4") (pin "B1") (pinfunction "P$2_B1") (pintype "bidirectional"))
      (node (ref "SIDE10") (pin "6") (pinfunction "6_6") (pintype "passive"))
    )
    (net (code "122") (name "Net-(A4D-P$2)") (class "Default")
      (node (ref "A4") (pin "B2") (pinfunction "P$2_B2") (pintype "bidirectional"))
      (node (ref "SIDE9") (pin "4") (pinfunction "4_4") (pintype "passive"))
    )
    (net (code "123") (name "Net-(A4E-P$2)") (class "Default")
      (node (ref "A4") (pin "C1") (pinfunction "P$2_C1") (pintype "bidirectional"))
      (node (ref "SIDE10") (pin "1") (pinfunction "1_1") (pintype "passive"))
      (node (ref "SIDE10") (pin "11") (pinfunction "11_11") (pintype "passive"))
      (node (ref "SIDE10") (pin "13") (pinfunction "13_13") (pintype "passive"))
      (node (ref "SIDE10") (pin "15") (pinfunction "15_15") (pintype "passive"))
      (node (ref "SIDE10") (pin "17") (pinfunction "17_17") (pintype "passive"))
      (node (ref "SIDE10") (pin "19") (pinfunction "19_19") (pintype "passive"))
      (node (ref "SIDE10") (pin "21") (pinfunction "21_21") (pintype "passive"))
      (node (ref "SIDE10") (pin "23") (pinfunction "23_23") (pintype "passive"))
      (node (ref "SIDE10") (pin "25") (pinfunction "25_25") (pintype "passive"))
      (node (ref "SIDE10") (pin "27") (pinfunction "27_27") (pintype "passive"))
      (node (ref "SIDE10") (pin "29") (pinfunction "29_29") (pintype "passive"))
      (node (ref "SIDE10") (pin "3") (pinfunction "3_3") (pintype "passive"))
      (node (ref "SIDE10") (pin "31") (pinfunction "31_31") (pintype "passive"))
      (node (ref "SIDE10") (pin "33") (pinfunction "33_33") (pintype "passive"))
      (node (ref "SIDE10") (pin "5") (pinfunction "5_5") (pintype "passive"))
      (node (ref "SIDE10") (pin "7") (pinfunction "7_7") (pintype "passive"))
      (node (ref "SIDE10") (pin "9") (pinfunction "9_9") (pintype "passive"))
    )
    (net (code "124") (name "Net-(A4F-P$2)") (class "Default")
      (node (ref "A4") (pin "C2") (pinfunction "P$2_C2") (pintype "bidirectional"))
      (node (ref "SIDE9") (pin "1") (pinfunction "1_1") (pintype "passive"))
      (node (ref "SIDE9") (pin "11") (pinfunction "11_11") (pintype "passive"))
      (node (ref "SIDE9") (pin "13") (pinfunction "13_13") (pintype "passive"))
      (node (ref "SIDE9") (pin "15") (pinfunction "15_15") (pintype "passive"))
      (node (ref "SIDE9") (pin "17") (pinfunction "17_17") (pintype "passive"))
      (node (ref "SIDE9") (pin "19") (pinfunction "19_19") (pintype "passive"))
      (node (ref "SIDE9") (pin "21") (pinfunction "21_21") (pintype "passive"))
      (node (ref "SIDE9") (pin "23") (pinfunction "23_23") (pintype "passive"))
      (node (ref "SIDE9") (pin "25") (pinfunction "25_25") (pintype "passive"))
      (node (ref "SIDE9") (pin "27") (pinfunction "27_27") (pintype "passive"))
      (node (ref "SIDE9") (pin "29") (pinfunction "29_29") (pintype "passive"))
      (node (ref "SIDE9") (pin "3") (pinfunction "3_3") (pintype "passive"))
      (node (ref "SIDE9") (pin "31") (pinfunction "31_31") (pintype "passive"))
      (node (ref "SIDE9") (pin "33") (pinfunction "33_33") (pintype "passive"))
      (node (ref "SIDE9") (pin "5") (pinfunction "5_5") (pintype "passive"))
      (node (ref "SIDE9") (pin "7") (pinfunction "7_7") (pintype "passive"))
      (node (ref "SIDE9") (pin "9") (pinfunction "9_9") (pintype "passive"))
    )
    (net (code "125") (name "Net-(A4G-P$2)") (class "Default")
      (node (ref "A4") (pin "D1") (pinfunction "P$2_D1") (pintype "bidirectional"))
      (node (ref "SIDE10") (pin "8") (pinfunction "8_8") (pintype "passive"))
    )
    (net (code "126") (name "Net-(A4H-P$2)") (class "Default")
      (node (ref "A4") (pin "D2") (pinfunction "P$2_D2") (pintype "bidirectional"))
      (node (ref "SIDE9") (pin "6") (pinfunction "6_6") (pintype "passive"))
    )
    (net (code "127") (name "Net-(A4I-P$2)") (class "Default")
      (node (ref "A4") (pin "E1") (pinfunction "P$2_E1") (pintype "bidirectional"))
      (node (ref "SIDE10") (pin "12") (pinfunction "12_12") (pintype "passive"))
    )
    (net (code "128") (name "Net-(A4J-P$2)") (class "Default")
      (node (ref "A4") (pin "E2") (pinfunction "P$2_E2") (pintype "bidirectional"))
      (node (ref "SIDE9") (pin "8") (pinfunction "8_8") (pintype "passive"))
    )
    (net (code "129") (name "Net-(A4K-P$2)") (class "Default")
      (node (ref "A4") (pin "F1") (pinfunction "P$2_F1") (pintype "bidirectional"))
      (node (ref "SIDE10") (pin "14") (pinfunction "14_14") (pintype "passive"))
    )
    (net (code "130") (name "Net-(A4L-P$2)") (class "Default")
      (node (ref "A4") (pin "F2") (pinfunction "P$2_F2") (pintype "bidirectional"))
      (node (ref "SIDE9") (pin "10") (pinfunction "10_10") (pintype "passive"))
    )
    (net (code "131") (name "Net-(A4M-P$2)") (class "Default")
      (node (ref "A4") (pin "H1") (pinfunction "P$2_H1") (pintype "bidirectional"))
      (node (ref "SIDE10") (pin "16") (pinfunction "16_16") (pintype "passive"))
    )
    (net (code "132") (name "Net-(A4N-P$2)") (class "Default")
      (node (ref "A4") (pin "H2") (pinfunction "P$2_H2") (pintype "bidirectional"))
      (node (ref "SIDE9") (pin "12") (pinfunction "12_12") (pintype "passive"))
    )
    (net (code "133") (name "Net-(A4O-P$2)") (class "Default")
      (node (ref "A4") (pin "J1") (pinfunction "P$2_J1") (pintype "bidirectional"))
      (node (ref "SIDE10") (pin "20") (pinfunction "20_20") (pintype "passive"))
    )
    (net (code "134") (name "Net-(A4P-P$2)") (class "Default")
      (node (ref "A4") (pin "J2") (pinfunction "P$2_J2") (pintype "bidirectional"))
      (node (ref "SIDE9") (pin "14") (pinfunction "14_14") (pintype "passive"))
    )
    (net (code "135") (name "Net-(A4Q-P$2)") (class "Default")
      (node (ref "A4") (pin "K1") (pinfunction "P$2_K1") (pintype "bidirectional"))
      (node (ref "SIDE10") (pin "18") (pinfunction "18_18") (pintype "passive"))
    )
    (net (code "136") (name "Net-(A4R-P$2)") (class "Default")
      (node (ref "A4") (pin "K2") (pinfunction "P$2_K2") (pintype "bidirectional"))
      (node (ref "SIDE9") (pin "16") (pinfunction "16_16") (pintype "passive"))
    )
    (net (code "137") (name "Net-(A4S-P$2)") (class "Default")
      (node (ref "A4") (pin "L1") (pinfunction "P$2_L1") (pintype "bidirectional"))
      (node (ref "SIDE10") (pin "24") (pinfunction "24_24") (pintype "passive"))
    )
    (net (code "138") (name "Net-(A4T-P$2)") (class "Default")
      (node (ref "A4") (pin "L2") (pinfunction "P$2_L2") (pintype "bidirectional"))
      (node (ref "SIDE9") (pin "18") (pinfunction "18_18") (pintype "passive"))
    )
    (net (code "139") (name "Net-(A4U-P$2)") (class "Default")
      (node (ref "A4") (pin "M1") (pinfunction "P$2_M1") (pintype "bidirectional"))
      (node (ref "SIDE10") (pin "28") (pinfunction "28_28") (pintype "passive"))
    )
    (net (code "140") (name "Net-(A4V-P$2)") (class "Default")
      (node (ref "A4") (pin "M2") (pinfunction "P$2_M2") (pintype "bidirectional"))
      (node (ref "SIDE9") (pin "20") (pinfunction "20_20") (pintype "passive"))
    )
    (net (code "141") (name "Net-(A4W-P$2)") (class "Default")
      (node (ref "A4") (pin "N1") (pinfunction "P$2_N1") (pintype "bidirectional"))
      (node (ref "SIDE10") (pin "22") (pinfunction "22_22") (pintype "passive"))
    )
    (net (code "142") (name "Net-(A4X-P$2)") (class "Default")
      (node (ref "A4") (pin "N2") (pinfunction "P$2_N2") (pintype "bidirectional"))
      (node (ref "SIDE9") (pin "22") (pinfunction "22_22") (pintype "passive"))
    )
    (net (code "143") (name "Net-(A4Y-P$2)") (class "Default")
      (node (ref "A4") (pin "P1") (pinfunction "P$2_P1") (pintype "bidirectional"))
      (node (ref "SIDE10") (pin "30") (pinfunction "30_30") (pintype "passive"))
    )
    (net (code "144") (name "Net-(A4Z-P$2)") (class "Default")
      (node (ref "A4") (pin "P2") (pinfunction "P$2_P2") (pintype "bidirectional"))
      (node (ref "SIDE9") (pin "24") (pinfunction "24_24") (pintype "passive"))
    )
    (net (code "145") (name "Net-(A5A-P$2)") (class "Default")
      (node (ref "A5") (pin "A1") (pinfunction "P$2_A1") (pintype "bidirectional"))
      (node (ref "SIDE1") (pin "10") (pinfunction "10_10") (pintype "passive"))
    )
    (net (code "146") (name "Net-(A5AA-P$2)") (class "Default")
      (node (ref "A5") (pin "R1") (pinfunction "P$2_R1") (pintype "bidirectional"))
      (node (ref "SIDE1") (pin "26") (pinfunction "26_26") (pintype "passive"))
    )
    (net (code "147") (name "Net-(A5AB-P$2)") (class "Default")
      (node (ref "A5") (pin "R2") (pinfunction "P$2_R2") (pintype "bidirectional"))
      (node (ref "SIDE2") (pin "26") (pinfunction "26_26") (pintype "passive"))
    )
    (net (code "148") (name "Net-(A5AC-P$2)") (class "Default")
      (node (ref "A5") (pin "S1") (pinfunction "P$2_S1") (pintype "bidirectional"))
      (node (ref "SIDE1") (pin "32") (pinfunction "32_32") (pintype "passive"))
    )
    (net (code "149") (name "Net-(A5AD-P$2)") (class "Default")
      (node (ref "A5") (pin "S2") (pinfunction "P$2_S2") (pintype "bidirectional"))
      (node (ref "SIDE2") (pin "28") (pinfunction "28_28") (pintype "passive"))
    )
    (net (code "150") (name "Net-(A5AE-P$2)") (class "Default")
      (node (ref "A5") (pin "T1") (pinfunction "P$2_T1") (pintype "bidirectional"))
      (node (ref "SIDE1") (pin "34") (pinfunction "34_34") (pintype "passive"))
    )
    (net (code "151") (name "Net-(A5AF-P$2)") (class "Default")
      (node (ref "A5") (pin "T2") (pinfunction "P$2_T2") (pintype "bidirectional"))
      (node (ref "SIDE2") (pin "30") (pinfunction "30_30") (pintype "passive"))
    )
    (net (code "152") (name "Net-(A5AG-P$2)") (class "Default")
      (node (ref "A5") (pin "U1") (pinfunction "P$2_U1") (pintype "bidirectional"))
      (node (ref "SIDE1") (pin "4") (pinfunction "4_4") (pintype "passive"))
    )
    (net (code "153") (name "Net-(A5AH-P$2)") (class "Default")
      (node (ref "A5") (pin "U2") (pinfunction "P$2_U2") (pintype "bidirectional"))
      (node (ref "SIDE2") (pin "34") (pinfunction "34_34") (pintype "passive"))
    )
    (net (code "154") (name "Net-(A5AI-P$2)") (class "Default")
      (node (ref "A5") (pin "V1") (pinfunction "P$2_V1") (pintype "bidirectional"))
      (node (ref "SIDE1") (pin "2") (pinfunction "2_2") (pintype "passive"))
    )
    (net (code "155") (name "Net-(A5AJ-P$2)") (class "Default")
      (node (ref "A5") (pin "V2") (pinfunction "P$2_V2") (pintype "bidirectional"))
      (node (ref "SIDE2") (pin "32") (pinfunction "32_32") (pintype "passive"))
    )
    (net (code "156") (name "Net-(A5B-P$2)") (class "Default")
      (node (ref "A5") (pin "A2") (pinfunction "P$2_A2") (pintype "bidirectional"))
      (node (ref "SIDE2") (pin "2") (pinfunction "2_2") (pintype "passive"))
    )
    (net (code "157") (name "Net-(A5C-P$2)") (class "Default")
      (node (ref "A5") (pin "B1") (pinfunction "P$2_B1") (pintype "bidirectional"))
      (node (ref "SIDE1") (pin "6") (pinfunction "6_6") (pintype "passive"))
    )
    (net (code "158") (name "Net-(A5D-P$2)") (class "Default")
      (node (ref "A5") (pin "B2") (pinfunction "P$2_B2") (pintype "bidirectional"))
      (node (ref "SIDE2") (pin "4") (pinfunction "4_4") (pintype "passive"))
    )
    (net (code "159") (name "Net-(A5E-P$2)") (class "Default")
      (node (ref "A5") (pin "C1") (pinfunction "P$2_C1") (pintype "bidirectional"))
      (node (ref "SIDE1") (pin "1") (pinfunction "1_1") (pintype "passive"))
      (node (ref "SIDE1") (pin "11") (pinfunction "11_11") (pintype "passive"))
      (node (ref "SIDE1") (pin "13") (pinfunction "13_13") (pintype "passive"))
      (node (ref "SIDE1") (pin "15") (pinfunction "15_15") (pintype "passive"))
      (node (ref "SIDE1") (pin "17") (pinfunction "17_17") (pintype "passive"))
      (node (ref "SIDE1") (pin "19") (pinfunction "19_19") (pintype "passive"))
      (node (ref "SIDE1") (pin "21") (pinfunction "21_21") (pintype "passive"))
      (node (ref "SIDE1") (pin "23") (pinfunction "23_23") (pintype "passive"))
      (node (ref "SIDE1") (pin "25") (pinfunction "25_25") (pintype "passive"))
      (node (ref "SIDE1") (pin "27") (pinfunction "27_27") (pintype "passive"))
      (node (ref "SIDE1") (pin "29") (pinfunction "29_29") (pintype "passive"))
      (node (ref "SIDE1") (pin "3") (pinfunction "3_3") (pintype "passive"))
      (node (ref "SIDE1") (pin "31") (pinfunction "31_31") (pintype "passive"))
      (node (ref "SIDE1") (pin "33") (pinfunction "33_33") (pintype "passive"))
      (node (ref "SIDE1") (pin "5") (pinfunction "5_5") (pintype "passive"))
      (node (ref "SIDE1") (pin "7") (pinfunction "7_7") (pintype "passive"))
      (node (ref "SIDE1") (pin "9") (pinfunction "9_9") (pintype "passive"))
    )
    (net (code "160") (name "Net-(A5F-P$2)") (class "Default")
      (node (ref "A5") (pin "C2") (pinfunction "P$2_C2") (pintype "bidirectional"))
      (node (ref "SIDE2") (pin "1") (pinfunction "1_1") (pintype "passive"))
      (node (ref "SIDE2") (pin "11") (pinfunction "11_11") (pintype "passive"))
      (node (ref "SIDE2") (pin "13") (pinfunction "13_13") (pintype "passive"))
      (node (ref "SIDE2") (pin "15") (pinfunction "15_15") (pintype "passive"))
      (node (ref "SIDE2") (pin "17") (pinfunction "17_17") (pintype "passive"))
      (node (ref "SIDE2") (pin "19") (pinfunction "19_19") (pintype "passive"))
      (node (ref "SIDE2") (pin "21") (pinfunction "21_21") (pintype "passive"))
      (node (ref "SIDE2") (pin "23") (pinfunction "23_23") (pintype "passive"))
      (node (ref "SIDE2") (pin "25") (pinfunction "25_25") (pintype "passive"))
      (node (ref "SIDE2") (pin "27") (pinfunction "27_27") (pintype "passive"))
      (node (ref "SIDE2") (pin "29") (pinfunction "29_29") (pintype "passive"))
      (node (ref "SIDE2") (pin "3") (pinfunction "3_3") (pintype "passive"))
      (node (ref "SIDE2") (pin "31") (pinfunction "31_31") (pintype "passive"))
      (node (ref "SIDE2") (pin "33") (pinfunction "33_33") (pintype "passive"))
      (node (ref "SIDE2") (pin "5") (pinfunction "5_5") (pintype "passive"))
      (node (ref "SIDE2") (pin "7") (pinfunction "7_7") (pintype "passive"))
      (node (ref "SIDE2") (pin "9") (pinfunction "9_9") (pintype "passive"))
    )
    (net (code "161") (name "Net-(A5G-P$2)") (class "Default")
      (node (ref "A5") (pin "D1") (pinfunction "P$2_D1") (pintype "bidirectional"))
      (node (ref "SIDE1") (pin "8") (pinfunction "8_8") (pintype "passive"))
    )
    (net (code "162") (name "Net-(A5H-P$2)") (class "Default")
      (node (ref "A5") (pin "D2") (pinfunction "P$2_D2") (pintype "bidirectional"))
      (node (ref "SIDE2") (pin "6") (pinfunction "6_6") (pintype "passive"))
    )
    (net (code "163") (name "Net-(A5I-P$2)") (class "Default")
      (node (ref "A5") (pin "E1") (pinfunction "P$2_E1") (pintype "bidirectional"))
      (node (ref "SIDE1") (pin "12") (pinfunction "12_12") (pintype "passive"))
    )
    (net (code "164") (name "Net-(A5J-P$2)") (class "Default")
      (node (ref "A5") (pin "E2") (pinfunction "P$2_E2") (pintype "bidirectional"))
      (node (ref "SIDE2") (pin "8") (pinfunction "8_8") (pintype "passive"))
    )
    (net (code "165") (name "Net-(A5K-P$2)") (class "Default")
      (node (ref "A5") (pin "F1") (pinfunction "P$2_F1") (pintype "bidirectional"))
      (node (ref "SIDE1") (pin "14") (pinfunction "14_14") (pintype "passive"))
    )
    (net (code "166") (name "Net-(A5L-P$2)") (class "Default")
      (node (ref "A5") (pin "F2") (pinfunction "P$2_F2") (pintype "bidirectional"))
      (node (ref "SIDE2") (pin "10") (pinfunction "10_10") (pintype "passive"))
    )
    (net (code "167") (name "Net-(A5M-P$2)") (class "Default")
      (node (ref "A5") (pin "H1") (pinfunction "P$2_H1") (pintype "bidirectional"))
      (node (ref "SIDE1") (pin "16") (pinfunction "16_16") (pintype "passive"))
    )
    (net (code "168") (name "Net-(A5N-P$2)") (class "Default")
      (node (ref "A5") (pin "H2") (pinfunction "P$2_H2") (pintype "bidirectional"))
      (node (ref "SIDE2") (pin "12") (pinfunction "12_12") (pintype "passive"))
    )
    (net (code "169") (name "Net-(A5O-P$2)") (class "Default")
      (node (ref "A5") (pin "J1") (pinfunction "P$2_J1") (pintype "bidirectional"))
      (node (ref "SIDE1") (pin "20") (pinfunction "20_20") (pintype "passive"))
    )
    (net (code "170") (name "Net-(A5P-P$2)") (class "Default")
      (node (ref "A5") (pin "J2") (pinfunction "P$2_J2") (pintype "bidirectional"))
      (node (ref "SIDE2") (pin "14") (pinfunction "14_14") (pintype "passive"))
    )
    (net (code "171") (name "Net-(A5Q-P$2)") (class "Default")
      (node (ref "A5") (pin "K1") (pinfunction "P$2_K1") (pintype "bidirectional"))
      (node (ref "SIDE1") (pin "18") (pinfunction "18_18") (pintype "passive"))
    )
    (net (code "172") (name "Net-(A5R-P$2)") (class "Default")
      (node (ref "A5") (pin "K2") (pinfunction "P$2_K2") (pintype "bidirectional"))
      (node (ref "SIDE2") (pin "16") (pinfunction "16_16") (pintype "passive"))
    )
    (net (code "173") (name "Net-(A5S-P$2)") (class "Default")
      (node (ref "A5") (pin "L1") (pinfunction "P$2_L1") (pintype "bidirectional"))
      (node (ref "SIDE1") (pin "24") (pinfunction "24_24") (pintype "passive"))
    )
    (net (code "174") (name "Net-(A5T-P$2)") (class "Default")
      (node (ref "A5") (pin "L2") (pinfunction "P$2_L2") (pintype "bidirectional"))
      (node (ref "SIDE2") (pin "18") (pinfunction "18_18") (pintype "passive"))
    )
    (net (code "175") (name "Net-(A5U-P$2)") (class "Default")
      (node (ref "A5") (pin "M1") (pinfunction "P$2_M1") (pintype "bidirectional"))
      (node (ref "SIDE1") (pin "28") (pinfunction "28_28") (pintype "passive"))
    )
    (net (code "176") (name "Net-(A5V-P$2)") (class "Default")
      (node (ref "A5") (pin "M2") (pinfunction "P$2_M2") (pintype "bidirectional"))
      (node (ref "SIDE2") (pin "20") (pinfunction "20_20") (pintype "passive"))
    )
    (net (code "177") (name "Net-(A5W-P$2)") (class "Default")
      (node (ref "A5") (pin "N1") (pinfunction "P$2_N1") (pintype "bidirectional"))
      (node (ref "SIDE1") (pin "22") (pinfunction "22_22") (pintype "passive"))
    )
    (net (code "178") (name "Net-(A5X-P$2)") (class "Default")
      (node (ref "A5") (pin "N2") (pinfunction "P$2_N2") (pintype "bidirectional"))
      (node (ref "SIDE2") (pin "22") (pinfunction "22_22") (pintype "passive"))
    )
    (net (code "179") (name "Net-(A5Y-P$2)") (class "Default")
      (node (ref "A5") (pin "P1") (pinfunction "P$2_P1") (pintype "bidirectional"))
      (node (ref "SIDE1") (pin "30") (pinfunction "30_30") (pintype "passive"))
    )
    (net (code "180") (name "Net-(A5Z-P$2)") (class "Default")
      (node (ref "A5") (pin "P2") (pinfunction "P$2_P2") (pintype "bidirectional"))
      (node (ref "SIDE2") (pin "24") (pinfunction "24_24") (pintype "passive"))
    )
    (net (code "181") (name "Net-(A6A-P$2)") (class "Default")
      (node (ref "A6") (pin "A1") (pinfunction "P$2_A1") (pintype "bidirectional"))
      (node (ref "SIDE12") (pin "10") (pinfunction "10_10") (pintype "passive"))
    )
    (net (code "182") (name "Net-(A6AA-P$2)") (class "Default")
      (node (ref "A6") (pin "R1") (pinfunction "P$2_R1") (pintype "bidirectional"))
      (node (ref "SIDE12") (pin "26") (pinfunction "26_26") (pintype "passive"))
    )
    (net (code "183") (name "Net-(A6AB-P$2)") (class "Default")
      (node (ref "A6") (pin "R2") (pinfunction "P$2_R2") (pintype "bidirectional"))
      (node (ref "SIDE11") (pin "26") (pinfunction "26_26") (pintype "passive"))
    )
    (net (code "184") (name "Net-(A6AC-P$2)") (class "Default")
      (node (ref "A6") (pin "S1") (pinfunction "P$2_S1") (pintype "bidirectional"))
      (node (ref "SIDE12") (pin "32") (pinfunction "32_32") (pintype "passive"))
    )
    (net (code "185") (name "Net-(A6AD-P$2)") (class "Default")
      (node (ref "A6") (pin "S2") (pinfunction "P$2_S2") (pintype "bidirectional"))
      (node (ref "SIDE11") (pin "28") (pinfunction "28_28") (pintype "passive"))
    )
    (net (code "186") (name "Net-(A6AE-P$2)") (class "Default")
      (node (ref "A6") (pin "T1") (pinfunction "P$2_T1") (pintype "bidirectional"))
      (node (ref "SIDE12") (pin "34") (pinfunction "34_34") (pintype "passive"))
    )
    (net (code "187") (name "Net-(A6AF-P$2)") (class "Default")
      (node (ref "A6") (pin "T2") (pinfunction "P$2_T2") (pintype "bidirectional"))
      (node (ref "SIDE11") (pin "30") (pinfunction "30_30") (pintype "passive"))
    )
    (net (code "188") (name "Net-(A6AG-P$2)") (class "Default")
      (node (ref "A6") (pin "U1") (pinfunction "P$2_U1") (pintype "bidirectional"))
      (node (ref "SIDE12") (pin "4") (pinfunction "4_4") (pintype "passive"))
    )
    (net (code "189") (name "Net-(A6AH-P$2)") (class "Default")
      (node (ref "A6") (pin "U2") (pinfunction "P$2_U2") (pintype "bidirectional"))
      (node (ref "SIDE11") (pin "34") (pinfunction "34_34") (pintype "passive"))
    )
    (net (code "190") (name "Net-(A6AI-P$2)") (class "Default")
      (node (ref "A6") (pin "V1") (pinfunction "P$2_V1") (pintype "bidirectional"))
      (node (ref "SIDE12") (pin "2") (pinfunction "2_2") (pintype "passive"))
    )
    (net (code "191") (name "Net-(A6AJ-P$2)") (class "Default")
      (node (ref "A6") (pin "V2") (pinfunction "P$2_V2") (pintype "bidirectional"))
      (node (ref "SIDE11") (pin "32") (pinfunction "32_32") (pintype "passive"))
    )
    (net (code "192") (name "Net-(A6B-P$2)") (class "Default")
      (node (ref "A6") (pin "A2") (pinfunction "P$2_A2") (pintype "bidirectional"))
      (node (ref "SIDE11") (pin "2") (pinfunction "2_2") (pintype "passive"))
    )
    (net (code "193") (name "Net-(A6C-P$2)") (class "Default")
      (node (ref "A6") (pin "B1") (pinfunction "P$2_B1") (pintype "bidirectional"))
      (node (ref "SIDE12") (pin "6") (pinfunction "6_6") (pintype "passive"))
    )
    (net (code "194") (name "Net-(A6D-P$2)") (class "Default")
      (node (ref "A6") (pin "B2") (pinfunction "P$2_B2") (pintype "bidirectional"))
      (node (ref "SIDE11") (pin "4") (pinfunction "4_4") (pintype "passive"))
    )
    (net (code "195") (name "Net-(A6E-P$2)") (class "Default")
      (node (ref "A6") (pin "C1") (pinfunction "P$2_C1") (pintype "bidirectional"))
      (node (ref "SIDE12") (pin "1") (pinfunction "1_1") (pintype "passive"))
      (node (ref "SIDE12") (pin "11") (pinfunction "11_11") (pintype "passive"))
      (node (ref "SIDE12") (pin "13") (pinfunction "13_13") (pintype "passive"))
      (node (ref "SIDE12") (pin "15") (pinfunction "15_15") (pintype "passive"))
      (node (ref "SIDE12") (pin "17") (pinfunction "17_17") (pintype "passive"))
      (node (ref "SIDE12") (pin "19") (pinfunction "19_19") (pintype "passive"))
      (node (ref "SIDE12") (pin "21") (pinfunction "21_21") (pintype "passive"))
      (node (ref "SIDE12") (pin "23") (pinfunction "23_23") (pintype "passive"))
      (node (ref "SIDE12") (pin "25") (pinfunction "25_25") (pintype "passive"))
      (node (ref "SIDE12") (pin "27") (pinfunction "27_27") (pintype "passive"))
      (node (ref "SIDE12") (pin "29") (pinfunction "29_29") (pintype "passive"))
      (node (ref "SIDE12") (pin "3") (pinfunction "3_3") (pintype "passive"))
      (node (ref "SIDE12") (pin "31") (pinfunction "31_31") (pintype "passive"))
      (node (ref "SIDE12") (pin "33") (pinfunction "33_33") (pintype "passive"))
      (node (ref "SIDE12") (pin "5") (pinfunction "5_5") (pintype "passive"))
      (node (ref "SIDE12") (pin "7") (pinfunction "7_7") (pintype "passive"))
      (node (ref "SIDE12") (pin "9") (pinfunction "9_9") (pintype "passive"))
    )
    (net (code "196") (name "Net-(A6F-P$2)") (class "Default")
      (node (ref "A6") (pin "C2") (pinfunction "P$2_C2") (pintype "bidirectional"))
      (node (ref "SIDE11") (pin "1") (pinfunction "1_1") (pintype "passive"))
      (node (ref "SIDE11") (pin "11") (pinfunction "11_11") (pintype "passive"))
      (node (ref "SIDE11") (pin "13") (pinfunction "13_13") (pintype "passive"))
      (node (ref "SIDE11") (pin "15") (pinfunction "15_15") (pintype "passive"))
      (node (ref "SIDE11") (pin "17") (pinfunction "17_17") (pintype "passive"))
      (node (ref "SIDE11") (pin "19") (pinfunction "19_19") (pintype "passive"))
      (node (ref "SIDE11") (pin "21") (pinfunction "21_21") (pintype "passive"))
      (node (ref "SIDE11") (pin "23") (pinfunction "23_23") (pintype "passive"))
      (node (ref "SIDE11") (pin "25") (pinfunction "25_25") (pintype "passive"))
      (node (ref "SIDE11") (pin "27") (pinfunction "27_27") (pintype "passive"))
      (node (ref "SIDE11") (pin "29") (pinfunction "29_29") (pintype "passive"))
      (node (ref "SIDE11") (pin "3") (pinfunction "3_3") (pintype "passive"))
      (node (ref "SIDE11") (pin "31") (pinfunction "31_31") (pintype "passive"))
      (node (ref "SIDE11") (pin "33") (pinfunction "33_33") (pintype "passive"))
      (node (ref "SIDE11") (pin "5") (pinfunction "5_5") (pintype "passive"))
      (node (ref "SIDE11") (pin "7") (pinfunction "7_7") (pintype "passive"))
      (node (ref "SIDE11") (pin "9") (pinfunction "9_9") (pintype "passive"))
    )
    (net (code "197") (name "Net-(A6G-P$2)") (class "Default")
      (node (ref "A6") (pin "D1") (pinfunction "P$2_D1") (pintype "bidirectional"))
      (node (ref "SIDE12") (pin "8") (pinfunction "8_8") (pintype "passive"))
    )
    (net (code "198") (name "Net-(A6H-P$2)") (class "Default")
      (node (ref "A6") (pin "D2") (pinfunction "P$2_D2") (pintype "bidirectional"))
      (node (ref "SIDE11") (pin "6") (pinfunction "6_6") (pintype "passive"))
    )
    (net (code "199") (name "Net-(A6I-P$2)") (class "Default")
      (node (ref "A6") (pin "E1") (pinfunction "P$2_E1") (pintype "bidirectional"))
      (node (ref "SIDE12") (pin "12") (pinfunction "12_12") (pintype "passive"))
    )
    (net (code "200") (name "Net-(A6J-P$2)") (class "Default")
      (node (ref "A6") (pin "E2") (pinfunction "P$2_E2") (pintype "bidirectional"))
      (node (ref "SIDE11") (pin "8") (pinfunction "8_8") (pintype "passive"))
    )
    (net (code "201") (name "Net-(A6K-P$2)") (class "Default")
      (node (ref "A6") (pin "F1") (pinfunction "P$2_F1") (pintype "bidirectional"))
      (node (ref "SIDE12") (pin "14") (pinfunction "14_14") (pintype "passive"))
    )
    (net (code "202") (name "Net-(A6L-P$2)") (class "Default")
      (node (ref "A6") (pin "F2") (pinfunction "P$2_F2") (pintype "bidirectional"))
      (node (ref "SIDE11") (pin "10") (pinfunction "10_10") (pintype "passive"))
    )
    (net (code "203") (name "Net-(A6M-P$2)") (class "Default")
      (node (ref "A6") (pin "H1") (pinfunction "P$2_H1") (pintype "bidirectional"))
      (node (ref "SIDE12") (pin "16") (pinfunction "16_16") (pintype "passive"))
    )
    (net (code "204") (name "Net-(A6N-P$2)") (class "Default")
      (node (ref "A6") (pin "H2") (pinfunction "P$2_H2") (pintype "bidirectional"))
      (node (ref "SIDE11") (pin "12") (pinfunction "12_12") (pintype "passive"))
    )
    (net (code "205") (name "Net-(A6O-P$2)") (class "Default")
      (node (ref "A6") (pin "J1") (pinfunction "P$2_J1") (pintype "bidirectional"))
      (node (ref "SIDE12") (pin "20") (pinfunction "20_20") (pintype "passive"))
    )
    (net (code "206") (name "Net-(A6P-P$2)") (class "Default")
      (node (ref "A6") (pin "J2") (pinfunction "P$2_J2") (pintype "bidirectional"))
      (node (ref "SIDE11") (pin "14") (pinfunction "14_14") (pintype "passive"))
    )
    (net (code "207") (name "Net-(A6Q-P$2)") (class "Default")
      (node (ref "A6") (pin "K1") (pinfunction "P$2_K1") (pintype "bidirectional"))
      (node (ref "SIDE12") (pin "18") (pinfunction "18_18") (pintype "passive"))
    )
    (net (code "208") (name "Net-(A6R-P$2)") (class "Default")
      (node (ref "A6") (pin "K2") (pinfunction "P$2_K2") (pintype "bidirectional"))
      (node (ref "SIDE11") (pin "16") (pinfunction "16_16") (pintype "passive"))
    )
    (net (code "209") (name "Net-(A6S-P$2)") (class "Default")
      (node (ref "A6") (pin "L1") (pinfunction "P$2_L1") (pintype "bidirectional"))
      (node (ref "SIDE12") (pin "24") (pinfunction "24_24") (pintype "passive"))
    )
    (net (code "210") (name "Net-(A6T-P$2)") (class "Default")
      (node (ref "A6") (pin "L2") (pinfunction "P$2_L2") (pintype "bidirectional"))
      (node (ref "SIDE11") (pin "18") (pinfunction "18_18") (pintype "passive"))
    )
    (net (code "211") (name "Net-(A6U-P$2)") (class "Default")
      (node (ref "A6") (pin "M1") (pinfunction "P$2_M1") (pintype "bidirectional"))
      (node (ref "SIDE12") (pin "28") (pinfunction "28_28") (pintype "passive"))
    )
    (net (code "212") (name "Net-(A6V-P$2)") (class "Default")
      (node (ref "A6") (pin "M2") (pinfunction "P$2_M2") (pintype "bidirectional"))
      (node (ref "SIDE11") (pin "20") (pinfunction "20_20") (pintype "passive"))
    )
    (net (code "213") (name "Net-(A6W-P$2)") (class "Default")
      (node (ref "A6") (pin "N1") (pinfunction "P$2_N1") (pintype "bidirectional"))
      (node (ref "SIDE12") (pin "22") (pinfunction "22_22") (pintype "passive"))
    )
    (net (code "214") (name "Net-(A6X-P$2)") (class "Default")
      (node (ref "A6") (pin "N2") (pinfunction "P$2_N2") (pintype "bidirectional"))
      (node (ref "SIDE11") (pin "22") (pinfunction "22_22") (pintype "passive"))
    )
    (net (code "215") (name "Net-(A6Y-P$2)") (class "Default")
      (node (ref "A6") (pin "P1") (pinfunction "P$2_P1") (pintype "bidirectional"))
      (node (ref "SIDE12") (pin "30") (pinfunction "30_30") (pintype "passive"))
    )
    (net (code "216") (name "Net-(A6Z-P$2)") (class "Default")
      (node (ref "A6") (pin "P2") (pinfunction "P$2_P2") (pintype "bidirectional"))
      (node (ref "SIDE11") (pin "24") (pinfunction "24_24") (pintype "passive"))
    )
    (net (code "217") (name "Net-(A7A-P$2)") (class "Default")
      (node (ref "A7") (pin "A1") (pinfunction "P$2_A1") (pintype "bidirectional"))
      (node (ref "SIDE14") (pin "10") (pinfunction "10_10") (pintype "passive"))
    )
    (net (code "218") (name "Net-(A7AA-P$2)") (class "Default")
      (node (ref "A7") (pin "R1") (pinfunction "P$2_R1") (pintype "bidirectional"))
      (node (ref "SIDE14") (pin "26") (pinfunction "26_26") (pintype "passive"))
    )
    (net (code "219") (name "Net-(A7AB-P$2)") (class "Default")
      (node (ref "A7") (pin "R2") (pinfunction "P$2_R2") (pintype "bidirectional"))
      (node (ref "SIDE13") (pin "26") (pinfunction "26_26") (pintype "passive"))
    )
    (net (code "220") (name "Net-(A7AC-P$2)") (class "Default")
      (node (ref "A7") (pin "S1") (pinfunction "P$2_S1") (pintype "bidirectional"))
      (node (ref "SIDE14") (pin "32") (pinfunction "32_32") (pintype "passive"))
    )
    (net (code "221") (name "Net-(A7AD-P$2)") (class "Default")
      (node (ref "A7") (pin "S2") (pinfunction "P$2_S2") (pintype "bidirectional"))
      (node (ref "SIDE13") (pin "28") (pinfunction "28_28") (pintype "passive"))
    )
    (net (code "222") (name "Net-(A7AE-P$2)") (class "Default")
      (node (ref "A7") (pin "T1") (pinfunction "P$2_T1") (pintype "bidirectional"))
      (node (ref "SIDE14") (pin "34") (pinfunction "34_34") (pintype "passive"))
    )
    (net (code "223") (name "Net-(A7AF-P$2)") (class "Default")
      (node (ref "A7") (pin "T2") (pinfunction "P$2_T2") (pintype "bidirectional"))
      (node (ref "SIDE13") (pin "30") (pinfunction "30_30") (pintype "passive"))
    )
    (net (code "224") (name "Net-(A7AG-P$2)") (class "Default")
      (node (ref "A7") (pin "U1") (pinfunction "P$2_U1") (pintype "bidirectional"))
      (node (ref "SIDE14") (pin "4") (pinfunction "4_4") (pintype "passive"))
    )
    (net (code "225") (name "Net-(A7AH-P$2)") (class "Default")
      (node (ref "A7") (pin "U2") (pinfunction "P$2_U2") (pintype "bidirectional"))
      (node (ref "SIDE13") (pin "34") (pinfunction "34_34") (pintype "passive"))
    )
    (net (code "226") (name "Net-(A7AI-P$2)") (class "Default")
      (node (ref "A7") (pin "V1") (pinfunction "P$2_V1") (pintype "bidirectional"))
      (node (ref "SIDE14") (pin "2") (pinfunction "2_2") (pintype "passive"))
    )
    (net (code "227") (name "Net-(A7AJ-P$2)") (class "Default")
      (node (ref "A7") (pin "V2") (pinfunction "P$2_V2") (pintype "bidirectional"))
      (node (ref "SIDE13") (pin "32") (pinfunction "32_32") (pintype "passive"))
    )
    (net (code "228") (name "Net-(A7B-P$2)") (class "Default")
      (node (ref "A7") (pin "A2") (pinfunction "P$2_A2") (pintype "bidirectional"))
      (node (ref "SIDE13") (pin "2") (pinfunction "2_2") (pintype "passive"))
    )
    (net (code "229") (name "Net-(A7C-P$2)") (class "Default")
      (node (ref "A7") (pin "B1") (pinfunction "P$2_B1") (pintype "bidirectional"))
      (node (ref "SIDE14") (pin "6") (pinfunction "6_6") (pintype "passive"))
    )
    (net (code "230") (name "Net-(A7D-P$2)") (class "Default")
      (node (ref "A7") (pin "B2") (pinfunction "P$2_B2") (pintype "bidirectional"))
      (node (ref "SIDE13") (pin "4") (pinfunction "4_4") (pintype "passive"))
    )
    (net (code "231") (name "Net-(A7E-P$2)") (class "Default")
      (node (ref "A7") (pin "C1") (pinfunction "P$2_C1") (pintype "bidirectional"))
      (node (ref "SIDE14") (pin "1") (pinfunction "1_1") (pintype "passive"))
      (node (ref "SIDE14") (pin "11") (pinfunction "11_11") (pintype "passive"))
      (node (ref "SIDE14") (pin "13") (pinfunction "13_13") (pintype "passive"))
      (node (ref "SIDE14") (pin "15") (pinfunction "15_15") (pintype "passive"))
      (node (ref "SIDE14") (pin "17") (pinfunction "17_17") (pintype "passive"))
      (node (ref "SIDE14") (pin "19") (pinfunction "19_19") (pintype "passive"))
      (node (ref "SIDE14") (pin "21") (pinfunction "21_21") (pintype "passive"))
      (node (ref "SIDE14") (pin "23") (pinfunction "23_23") (pintype "passive"))
      (node (ref "SIDE14") (pin "25") (pinfunction "25_25") (pintype "passive"))
      (node (ref "SIDE14") (pin "27") (pinfunction "27_27") (pintype "passive"))
      (node (ref "SIDE14") (pin "29") (pinfunction "29_29") (pintype "passive"))
      (node (ref "SIDE14") (pin "3") (pinfunction "3_3") (pintype "passive"))
      (node (ref "SIDE14") (pin "31") (pinfunction "31_31") (pintype "passive"))
      (node (ref "SIDE14") (pin "33") (pinfunction "33_33") (pintype "passive"))
      (node (ref "SIDE14") (pin "5") (pinfunction "5_5") (pintype "passive"))
      (node (ref "SIDE14") (pin "7") (pinfunction "7_7") (pintype "passive"))
      (node (ref "SIDE14") (pin "9") (pinfunction "9_9") (pintype "passive"))
    )
    (net (code "232") (name "Net-(A7F-P$2)") (class "Default")
      (node (ref "A7") (pin "C2") (pinfunction "P$2_C2") (pintype "bidirectional"))
      (node (ref "SIDE13") (pin "1") (pinfunction "1_1") (pintype "passive"))
      (node (ref "SIDE13") (pin "11") (pinfunction "11_11") (pintype "passive"))
      (node (ref "SIDE13") (pin "13") (pinfunction "13_13") (pintype "passive"))
      (node (ref "SIDE13") (pin "15") (pinfunction "15_15") (pintype "passive"))
      (node (ref "SIDE13") (pin "17") (pinfunction "17_17") (pintype "passive"))
      (node (ref "SIDE13") (pin "19") (pinfunction "19_19") (pintype "passive"))
      (node (ref "SIDE13") (pin "21") (pinfunction "21_21") (pintype "passive"))
      (node (ref "SIDE13") (pin "23") (pinfunction "23_23") (pintype "passive"))
      (node (ref "SIDE13") (pin "25") (pinfunction "25_25") (pintype "passive"))
      (node (ref "SIDE13") (pin "27") (pinfunction "27_27") (pintype "passive"))
      (node (ref "SIDE13") (pin "29") (pinfunction "29_29") (pintype "passive"))
      (node (ref "SIDE13") (pin "3") (pinfunction "3_3") (pintype "passive"))
      (node (ref "SIDE13") (pin "31") (pinfunction "31_31") (pintype "passive"))
      (node (ref "SIDE13") (pin "33") (pinfunction "33_33") (pintype "passive"))
      (node (ref "SIDE13") (pin "5") (pinfunction "5_5") (pintype "passive"))
      (node (ref "SIDE13") (pin "7") (pinfunction "7_7") (pintype "passive"))
      (node (ref "SIDE13") (pin "9") (pinfunction "9_9") (pintype "passive"))
    )
    (net (code "233") (name "Net-(A7G-P$2)") (class "Default")
      (node (ref "A7") (pin "D1") (pinfunction "P$2_D1") (pintype "bidirectional"))
      (node (ref "SIDE14") (pin "8") (pinfunction "8_8") (pintype "passive"))
    )
    (net (code "234") (name "Net-(A7H-P$2)") (class "Default")
      (node (ref "A7") (pin "D2") (pinfunction "P$2_D2") (pintype "bidirectional"))
      (node (ref "SIDE13") (pin "6") (pinfunction "6_6") (pintype "passive"))
    )
    (net (code "235") (name "Net-(A7I-P$2)") (class "Default")
      (node (ref "A7") (pin "E1") (pinfunction "P$2_E1") (pintype "bidirectional"))
      (node (ref "SIDE14") (pin "12") (pinfunction "12_12") (pintype "passive"))
    )
    (net (code "236") (name "Net-(A7J-P$2)") (class "Default")
      (node (ref "A7") (pin "E2") (pinfunction "P$2_E2") (pintype "bidirectional"))
      (node (ref "SIDE13") (pin "8") (pinfunction "8_8") (pintype "passive"))
    )
    (net (code "237") (name "Net-(A7K-P$2)") (class "Default")
      (node (ref "A7") (pin "F1") (pinfunction "P$2_F1") (pintype "bidirectional"))
      (node (ref "SIDE14") (pin "14") (pinfunction "14_14") (pintype "passive"))
    )
    (net (code "238") (name "Net-(A7L-P$2)") (class "Default")
      (node (ref "A7") (pin "F2") (pinfunction "P$2_F2") (pintype "bidirectional"))
      (node (ref "SIDE13") (pin "10") (pinfunction "10_10") (pintype "passive"))
    )
    (net (code "239") (name "Net-(A7M-P$2)") (class "Default")
      (node (ref "A7") (pin "H1") (pinfunction "P$2_H1") (pintype "bidirectional"))
      (node (ref "SIDE14") (pin "16") (pinfunction "16_16") (pintype "passive"))
    )
    (net (code "240") (name "Net-(A7N-P$2)") (class "Default")
      (node (ref "A7") (pin "H2") (pinfunction "P$2_H2") (pintype "bidirectional"))
      (node (ref "SIDE13") (pin "12") (pinfunction "12_12") (pintype "passive"))
    )
    (net (code "241") (name "Net-(A7O-P$2)") (class "Default")
      (node (ref "A7") (pin "J1") (pinfunction "P$2_J1") (pintype "bidirectional"))
      (node (ref "SIDE14") (pin "20") (pinfunction "20_20") (pintype "passive"))
    )
    (net (code "242") (name "Net-(A7P-P$2)") (class "Default")
      (node (ref "A7") (pin "J2") (pinfunction "P$2_J2") (pintype "bidirectional"))
      (node (ref "SIDE13") (pin "14") (pinfunction "14_14") (pintype "passive"))
    )
    (net (code "243") (name "Net-(A7Q-P$2)") (class "Default")
      (node (ref "A7") (pin "K1") (pinfunction "P$2_K1") (pintype "bidirectional"))
      (node (ref "SIDE14") (pin "18") (pinfunction "18_18") (pintype "passive"))
    )
    (net (code "244") (name "Net-(A7R-P$2)") (class "Default")
      (node (ref "A7") (pin "K2") (pinfunction "P$2_K2") (pintype "bidirectional"))
      (node (ref "SIDE13") (pin "16") (pinfunction "16_16") (pintype "passive"))
    )
    (net (code "245") (name "Net-(A7S-P$2)") (class "Default")
      (node (ref "A7") (pin "L1") (pinfunction "P$2_L1") (pintype "bidirectional"))
      (node (ref "SIDE14") (pin "24") (pinfunction "24_24") (pintype "passive"))
    )
    (net (code "246") (name "Net-(A7T-P$2)") (class "Default")
      (node (ref "A7") (pin "L2") (pinfunction "P$2_L2") (pintype "bidirectional"))
      (node (ref "SIDE13") (pin "18") (pinfunction "18_18") (pintype "passive"))
    )
    (net (code "247") (name "Net-(A7U-P$2)") (class "Default")
      (node (ref "A7") (pin "M1") (pinfunction "P$2_M1") (pintype "bidirectional"))
      (node (ref "SIDE14") (pin "28") (pinfunction "28_28") (pintype "passive"))
    )
    (net (code "248") (name "Net-(A7V-P$2)") (class "Default")
      (node (ref "A7") (pin "M2") (pinfunction "P$2_M2") (pintype "bidirectional"))
      (node (ref "SIDE13") (pin "20") (pinfunction "20_20") (pintype "passive"))
    )
    (net (code "249") (name "Net-(A7W-P$2)") (class "Default")
      (node (ref "A7") (pin "N1") (pinfunction "P$2_N1") (pintype "bidirectional"))
      (node (ref "SIDE14") (pin "22") (pinfunction "22_22") (pintype "passive"))
    )
    (net (code "250") (name "Net-(A7X-P$2)") (class "Default")
      (node (ref "A7") (pin "N2") (pinfunction "P$2_N2") (pintype "bidirectional"))
      (node (ref "SIDE13") (pin "22") (pinfunction "22_22") (pintype "passive"))
    )
    (net (code "251") (name "Net-(A7Y-P$2)") (class "Default")
      (node (ref "A7") (pin "P1") (pinfunction "P$2_P1") (pintype "bidirectional"))
      (node (ref "SIDE14") (pin "30") (pinfunction "30_30") (pintype "passive"))
    )
    (net (code "252") (name "Net-(A7Z-P$2)") (class "Default")
      (node (ref "A7") (pin "P2") (pinfunction "P$2_P2") (pintype "bidirectional"))
      (node (ref "SIDE13") (pin "24") (pinfunction "24_24") (pintype "passive"))
    )
    (net (code "253") (name "Net-(A8A-P$2)") (class "Default")
      (node (ref "A8") (pin "A1") (pinfunction "P$2_A1") (pintype "bidirectional"))
      (node (ref "SIDE16") (pin "10") (pinfunction "10_10") (pintype "passive"))
    )
    (net (code "254") (name "Net-(A8AA-P$2)") (class "Default")
      (node (ref "A8") (pin "R1") (pinfunction "P$2_R1") (pintype "bidirectional"))
      (node (ref "SIDE16") (pin "26") (pinfunction "26_26") (pintype "passive"))
    )
    (net (code "255") (name "Net-(A8AB-P$2)") (class "Default")
      (node (ref "A8") (pin "R2") (pinfunction "P$2_R2") (pintype "bidirectional"))
      (node (ref "SIDE15") (pin "26") (pinfunction "26_26") (pintype "passive"))
    )
    (net (code "256") (name "Net-(A8AC-P$2)") (class "Default")
      (node (ref "A8") (pin "S1") (pinfunction "P$2_S1") (pintype "bidirectional"))
      (node (ref "SIDE16") (pin "32") (pinfunction "32_32") (pintype "passive"))
    )
    (net (code "257") (name "Net-(A8AD-P$2)") (class "Default")
      (node (ref "A8") (pin "S2") (pinfunction "P$2_S2") (pintype "bidirectional"))
      (node (ref "SIDE15") (pin "28") (pinfunction "28_28") (pintype "passive"))
    )
    (net (code "258") (name "Net-(A8AE-P$2)") (class "Default")
      (node (ref "A8") (pin "T1") (pinfunction "P$2_T1") (pintype "bidirectional"))
      (node (ref "SIDE16") (pin "34") (pinfunction "34_34") (pintype "passive"))
    )
    (net (code "259") (name "Net-(A8AF-P$2)") (class "Default")
      (node (ref "A8") (pin "T2") (pinfunction "P$2_T2") (pintype "bidirectional"))
      (node (ref "SIDE15") (pin "30") (pinfunction "30_30") (pintype "passive"))
    )
    (net (code "260") (name "Net-(A8AG-P$2)") (class "Default")
      (node (ref "A8") (pin "U1") (pinfunction "P$2_U1") (pintype "bidirectional"))
      (node (ref "SIDE16") (pin "4") (pinfunction "4_4") (pintype "passive"))
    )
    (net (code "261") (name "Net-(A8AH-P$2)") (class "Default")
      (node (ref "A8") (pin "U2") (pinfunction "P$2_U2") (pintype "bidirectional"))
      (node (ref "SIDE15") (pin "34") (pinfunction "34_34") (pintype "passive"))
    )
    (net (code "262") (name "Net-(A8AI-P$2)") (class "Default")
      (node (ref "A8") (pin "V1") (pinfunction "P$2_V1") (pintype "bidirectional"))
      (node (ref "SIDE16") (pin "2") (pinfunction "2_2") (pintype "passive"))
    )
    (net (code "263") (name "Net-(A8AJ-P$2)") (class "Default")
      (node (ref "A8") (pin "V2") (pinfunction "P$2_V2") (pintype "bidirectional"))
      (node (ref "SIDE15") (pin "32") (pinfunction "32_32") (pintype "passive"))
    )
    (net (code "264") (name "Net-(A8B-P$2)") (class "Default")
      (node (ref "A8") (pin "A2") (pinfunction "P$2_A2") (pintype "bidirectional"))
      (node (ref "SIDE15") (pin "2") (pinfunction "2_2") (pintype "passive"))
    )
    (net (code "265") (name "Net-(A8C-P$2)") (class "Default")
      (node (ref "A8") (pin "B1") (pinfunction "P$2_B1") (pintype "bidirectional"))
      (node (ref "SIDE16") (pin "6") (pinfunction "6_6") (pintype "passive"))
    )
    (net (code "266") (name "Net-(A8D-P$2)") (class "Default")
      (node (ref "A8") (pin "B2") (pinfunction "P$2_B2") (pintype "bidirectional"))
      (node (ref "SIDE15") (pin "4") (pinfunction "4_4") (pintype "passive"))
    )
    (net (code "267") (name "Net-(A8E-P$2)") (class "Default")
      (node (ref "A8") (pin "C1") (pinfunction "P$2_C1") (pintype "bidirectional"))
      (node (ref "SIDE16") (pin "1") (pinfunction "1_1") (pintype "passive"))
      (node (ref "SIDE16") (pin "11") (pinfunction "11_11") (pintype "passive"))
      (node (ref "SIDE16") (pin "13") (pinfunction "13_13") (pintype "passive"))
      (node (ref "SIDE16") (pin "15") (pinfunction "15_15") (pintype "passive"))
      (node (ref "SIDE16") (pin "17") (pinfunction "17_17") (pintype "passive"))
      (node (ref "SIDE16") (pin "19") (pinfunction "19_19") (pintype "passive"))
      (node (ref "SIDE16") (pin "21") (pinfunction "21_21") (pintype "passive"))
      (node (ref "SIDE16") (pin "23") (pinfunction "23_23") (pintype "passive"))
      (node (ref "SIDE16") (pin "25") (pinfunction "25_25") (pintype "passive"))
      (node (ref "SIDE16") (pin "27") (pinfunction "27_27") (pintype "passive"))
      (node (ref "SIDE16") (pin "29") (pinfunction "29_29") (pintype "passive"))
      (node (ref "SIDE16") (pin "3") (pinfunction "3_3") (pintype "passive"))
      (node (ref "SIDE16") (pin "31") (pinfunction "31_31") (pintype "passive"))
      (node (ref "SIDE16") (pin "33") (pinfunction "33_33") (pintype "passive"))
      (node (ref "SIDE16") (pin "5") (pinfunction "5_5") (pintype "passive"))
      (node (ref "SIDE16") (pin "7") (pinfunction "7_7") (pintype "passive"))
      (node (ref "SIDE16") (pin "9") (pinfunction "9_9") (pintype "passive"))
    )
    (net (code "268") (name "Net-(A8F-P$2)") (class "Default")
      (node (ref "A8") (pin "C2") (pinfunction "P$2_C2") (pintype "bidirectional"))
      (node (ref "SIDE15") (pin "1") (pinfunction "1_1") (pintype "passive"))
      (node (ref "SIDE15") (pin "11") (pinfunction "11_11") (pintype "passive"))
      (node (ref "SIDE15") (pin "13") (pinfunction "13_13") (pintype "passive"))
      (node (ref "SIDE15") (pin "15") (pinfunction "15_15") (pintype "passive"))
      (node (ref "SIDE15") (pin "17") (pinfunction "17_17") (pintype "passive"))
      (node (ref "SIDE15") (pin "19") (pinfunction "19_19") (pintype "passive"))
      (node (ref "SIDE15") (pin "21") (pinfunction "21_21") (pintype "passive"))
      (node (ref "SIDE15") (pin "23") (pinfunction "23_23") (pintype "passive"))
      (node (ref "SIDE15") (pin "25") (pinfunction "25_25") (pintype "passive"))
      (node (ref "SIDE15") (pin "27") (pinfunction "27_27") (pintype "passive"))
      (node (ref "SIDE15") (pin "29") (pinfunction "29_29") (pintype "passive"))
      (node (ref "SIDE15") (pin "3") (pinfunction "3_3") (pintype "passive"))
      (node (ref "SIDE15") (pin "31") (pinfunction "31_31") (pintype "passive"))
      (node (ref "SIDE15") (pin "33") (pinfunction "33_33") (pintype "passive"))
      (node (ref "SIDE15") (pin "5") (pinfunction "5_5") (pintype "passive"))
      (node (ref "SIDE15") (pin "7") (pinfunction "7_7") (pintype "passive"))
      (node (ref "SIDE15") (pin "9") (pinfunction "9_9") (pintype "passive"))
    )
    (net (code "269") (name "Net-(A8G-P$2)") (class "Default")
      (node (ref "A8") (pin "D1") (pinfunction "P$2_D1") (pintype "bidirectional"))
      (node (ref "SIDE16") (pin "8") (pinfunction "8_8") (pintype "passive"))
    )
    (net (code "270") (name "Net-(A8H-P$2)") (class "Default")
      (node (ref "A8") (pin "D2") (pinfunction "P$2_D2") (pintype "bidirectional"))
      (node (ref "SIDE15") (pin "6") (pinfunction "6_6") (pintype "passive"))
    )
    (net (code "271") (name "Net-(A8I-P$2)") (class "Default")
      (node (ref "A8") (pin "E1") (pinfunction "P$2_E1") (pintype "bidirectional"))
      (node (ref "SIDE16") (pin "12") (pinfunction "12_12") (pintype "passive"))
    )
    (net (code "272") (name "Net-(A8J-P$2)") (class "Default")
      (node (ref "A8") (pin "E2") (pinfunction "P$2_E2") (pintype "bidirectional"))
      (node (ref "SIDE15") (pin "8") (pinfunction "8_8") (pintype "passive"))
    )
    (net (code "273") (name "Net-(A8K-P$2)") (class "Default")
      (node (ref "A8") (pin "F1") (pinfunction "P$2_F1") (pintype "bidirectional"))
      (node (ref "SIDE16") (pin "14") (pinfunction "14_14") (pintype "passive"))
    )
    (net (code "274") (name "Net-(A8L-P$2)") (class "Default")
      (node (ref "A8") (pin "F2") (pinfunction "P$2_F2") (pintype "bidirectional"))
      (node (ref "SIDE15") (pin "10") (pinfunction "10_10") (pintype "passive"))
    )
    (net (code "275") (name "Net-(A8M-P$2)") (class "Default")
      (node (ref "A8") (pin "H1") (pinfunction "P$2_H1") (pintype "bidirectional"))
      (node (ref "SIDE16") (pin "16") (pinfunction "16_16") (pintype "passive"))
    )
    (net (code "276") (name "Net-(A8N-P$2)") (class "Default")
      (node (ref "A8") (pin "H2") (pinfunction "P$2_H2") (pintype "bidirectional"))
      (node (ref "SIDE15") (pin "12") (pinfunction "12_12") (pintype "passive"))
    )
    (net (code "277") (name "Net-(A8O-P$2)") (class "Default")
      (node (ref "A8") (pin "J1") (pinfunction "P$2_J1") (pintype "bidirectional"))
      (node (ref "SIDE16") (pin "20") (pinfunction "20_20") (pintype "passive"))
    )
    (net (code "278") (name "Net-(A8P-P$2)") (class "Default")
      (node (ref "A8") (pin "J2") (pinfunction "P$2_J2") (pintype "bidirectional"))
      (node (ref "SIDE15") (pin "14") (pinfunction "14_14") (pintype "passive"))
    )
    (net (code "279") (name "Net-(A8Q-P$2)") (class "Default")
      (node (ref "A8") (pin "K1") (pinfunction "P$2_K1") (pintype "bidirectional"))
      (node (ref "SIDE16") (pin "18") (pinfunction "18_18") (pintype "passive"))
    )
    (net (code "280") (name "Net-(A8R-P$2)") (class "Default")
      (node (ref "A8") (pin "K2") (pinfunction "P$2_K2") (pintype "bidirectional"))
      (node (ref "SIDE15") (pin "16") (pinfunction "16_16") (pintype "passive"))
    )
    (net (code "281") (name "Net-(A8S-P$2)") (class "Default")
      (node (ref "A8") (pin "L1") (pinfunction "P$2_L1") (pintype "bidirectional"))
      (node (ref "SIDE16") (pin "24") (pinfunction "24_24") (pintype "passive"))
    )
    (net (code "282") (name "Net-(A8T-P$2)") (class "Default")
      (node (ref "A8") (pin "L2") (pinfunction "P$2_L2") (pintype "bidirectional"))
      (node (ref "SIDE15") (pin "18") (pinfunction "18_18") (pintype "passive"))
    )
    (net (code "283") (name "Net-(A8U-P$2)") (class "Default")
      (node (ref "A8") (pin "M1") (pinfunction "P$2_M1") (pintype "bidirectional"))
      (node (ref "SIDE16") (pin "28") (pinfunction "28_28") (pintype "passive"))
    )
    (net (code "284") (name "Net-(A8V-P$2)") (class "Default")
      (node (ref "A8") (pin "M2") (pinfunction "P$2_M2") (pintype "bidirectional"))
      (node (ref "SIDE15") (pin "20") (pinfunction "20_20") (pintype "passive"))
    )
    (net (code "285") (name "Net-(A8W-P$2)") (class "Default")
      (node (ref "A8") (pin "N1") (pinfunction "P$2_N1") (pintype "bidirectional"))
      (node (ref "SIDE16") (pin "22") (pinfunction "22_22") (pintype "passive"))
    )
    (net (code "286") (name "Net-(A8X-P$2)") (class "Default")
      (node (ref "A8") (pin "N2") (pinfunction "P$2_N2") (pintype "bidirectional"))
      (node (ref "SIDE15") (pin "22") (pinfunction "22_22") (pintype "passive"))
    )
    (net (code "287") (name "Net-(A8Y-P$2)") (class "Default")
      (node (ref "A8") (pin "P1") (pinfunction "P$2_P1") (pintype "bidirectional"))
      (node (ref "SIDE16") (pin "30") (pinfunction "30_30") (pintype "passive"))
    )
    (net (code "288") (name "Net-(A8Z-P$2)") (class "Default")
      (node (ref "A8") (pin "P2") (pinfunction "P$2_P2") (pintype "bidirectional"))
      (node (ref "SIDE15") (pin "24") (pinfunction "24_24") (pintype "passive"))
    )
  )
)
